# Servosolenoidvalve_of_Tatebayashi.net
KiCad netlist of a schematic drawn in EAGLE
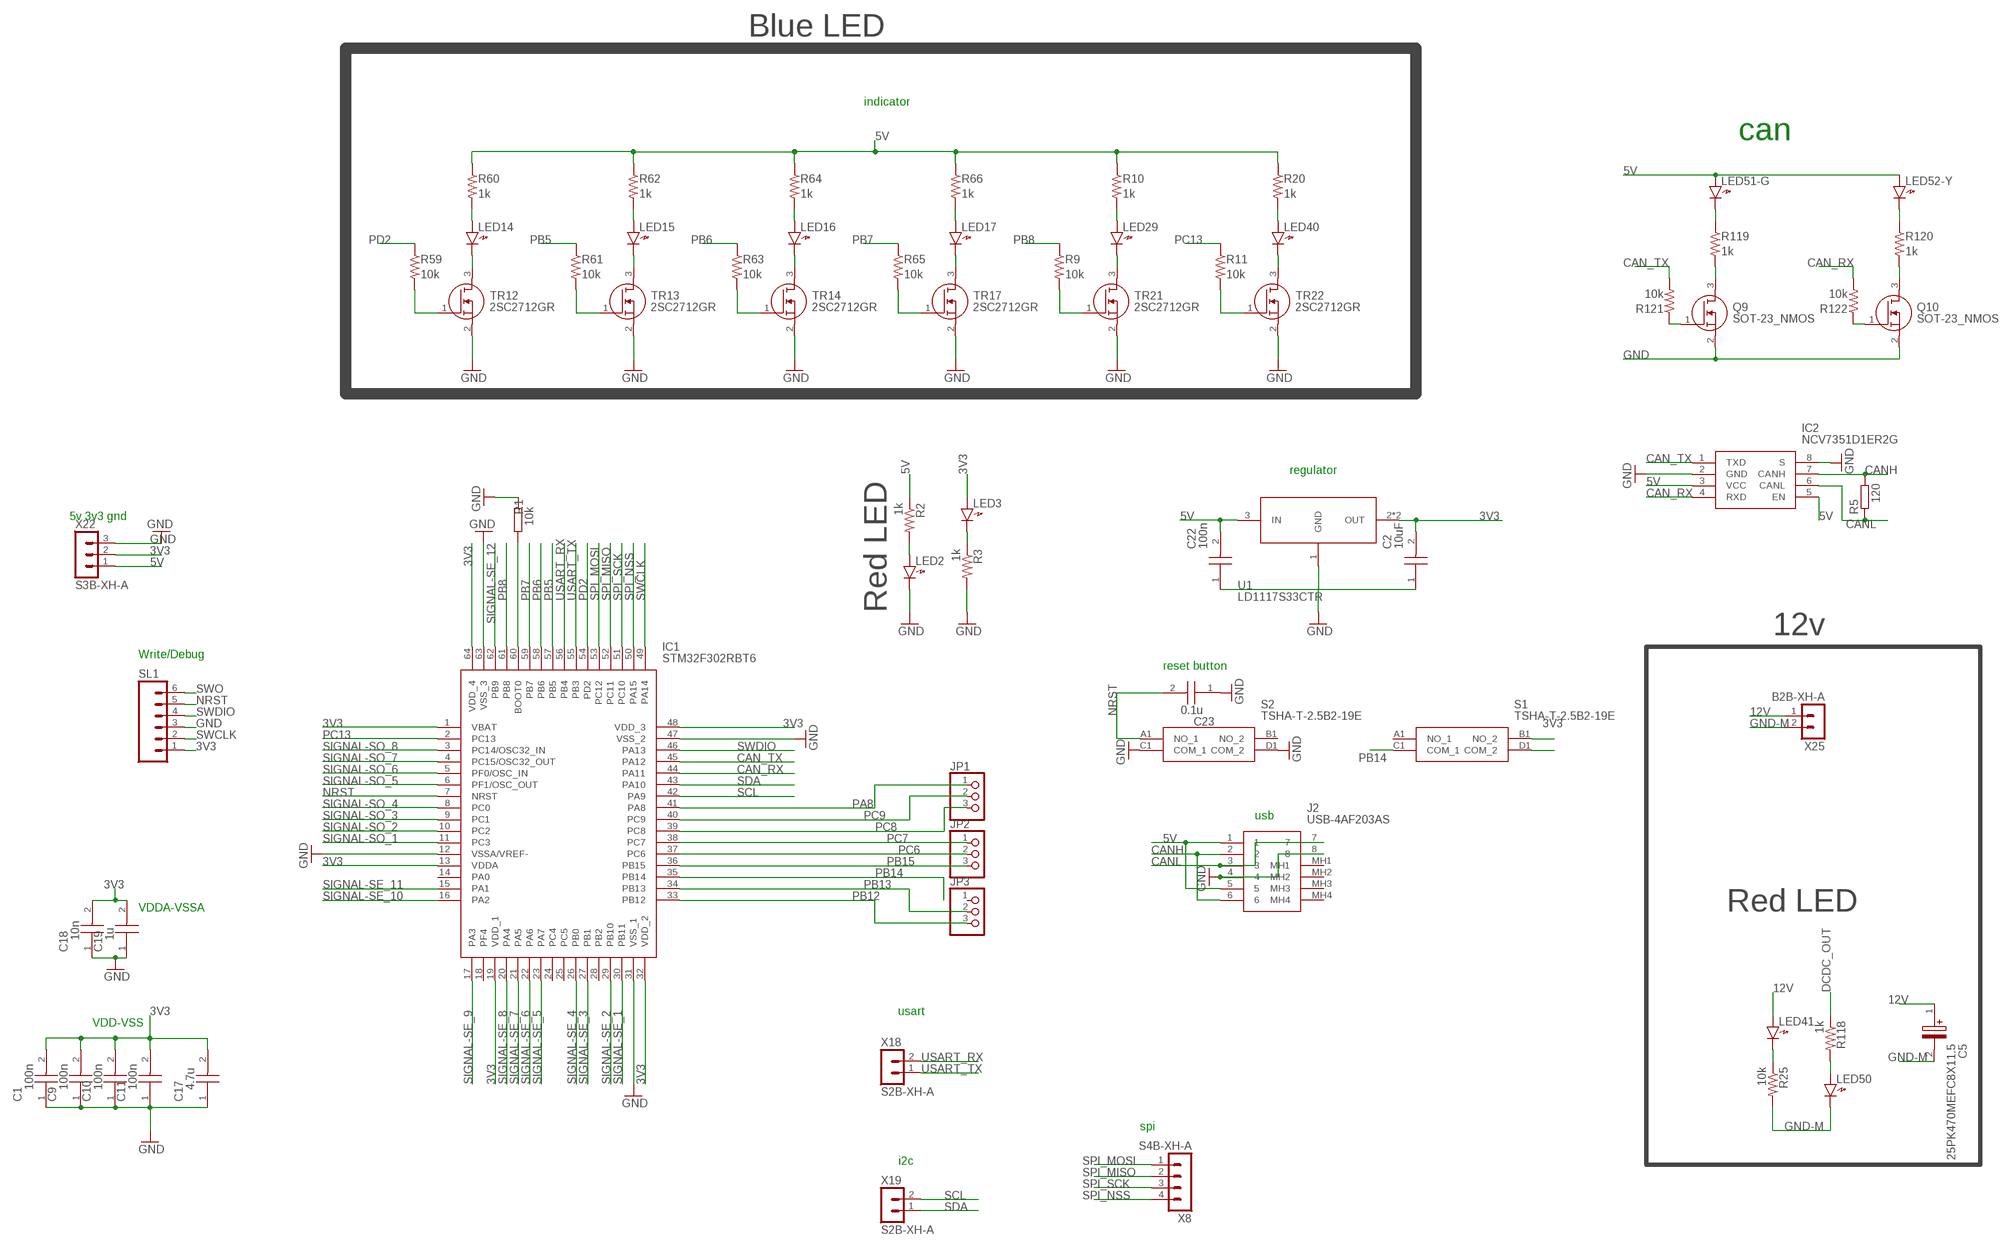
[diagram p0: schematic, sheet 1]
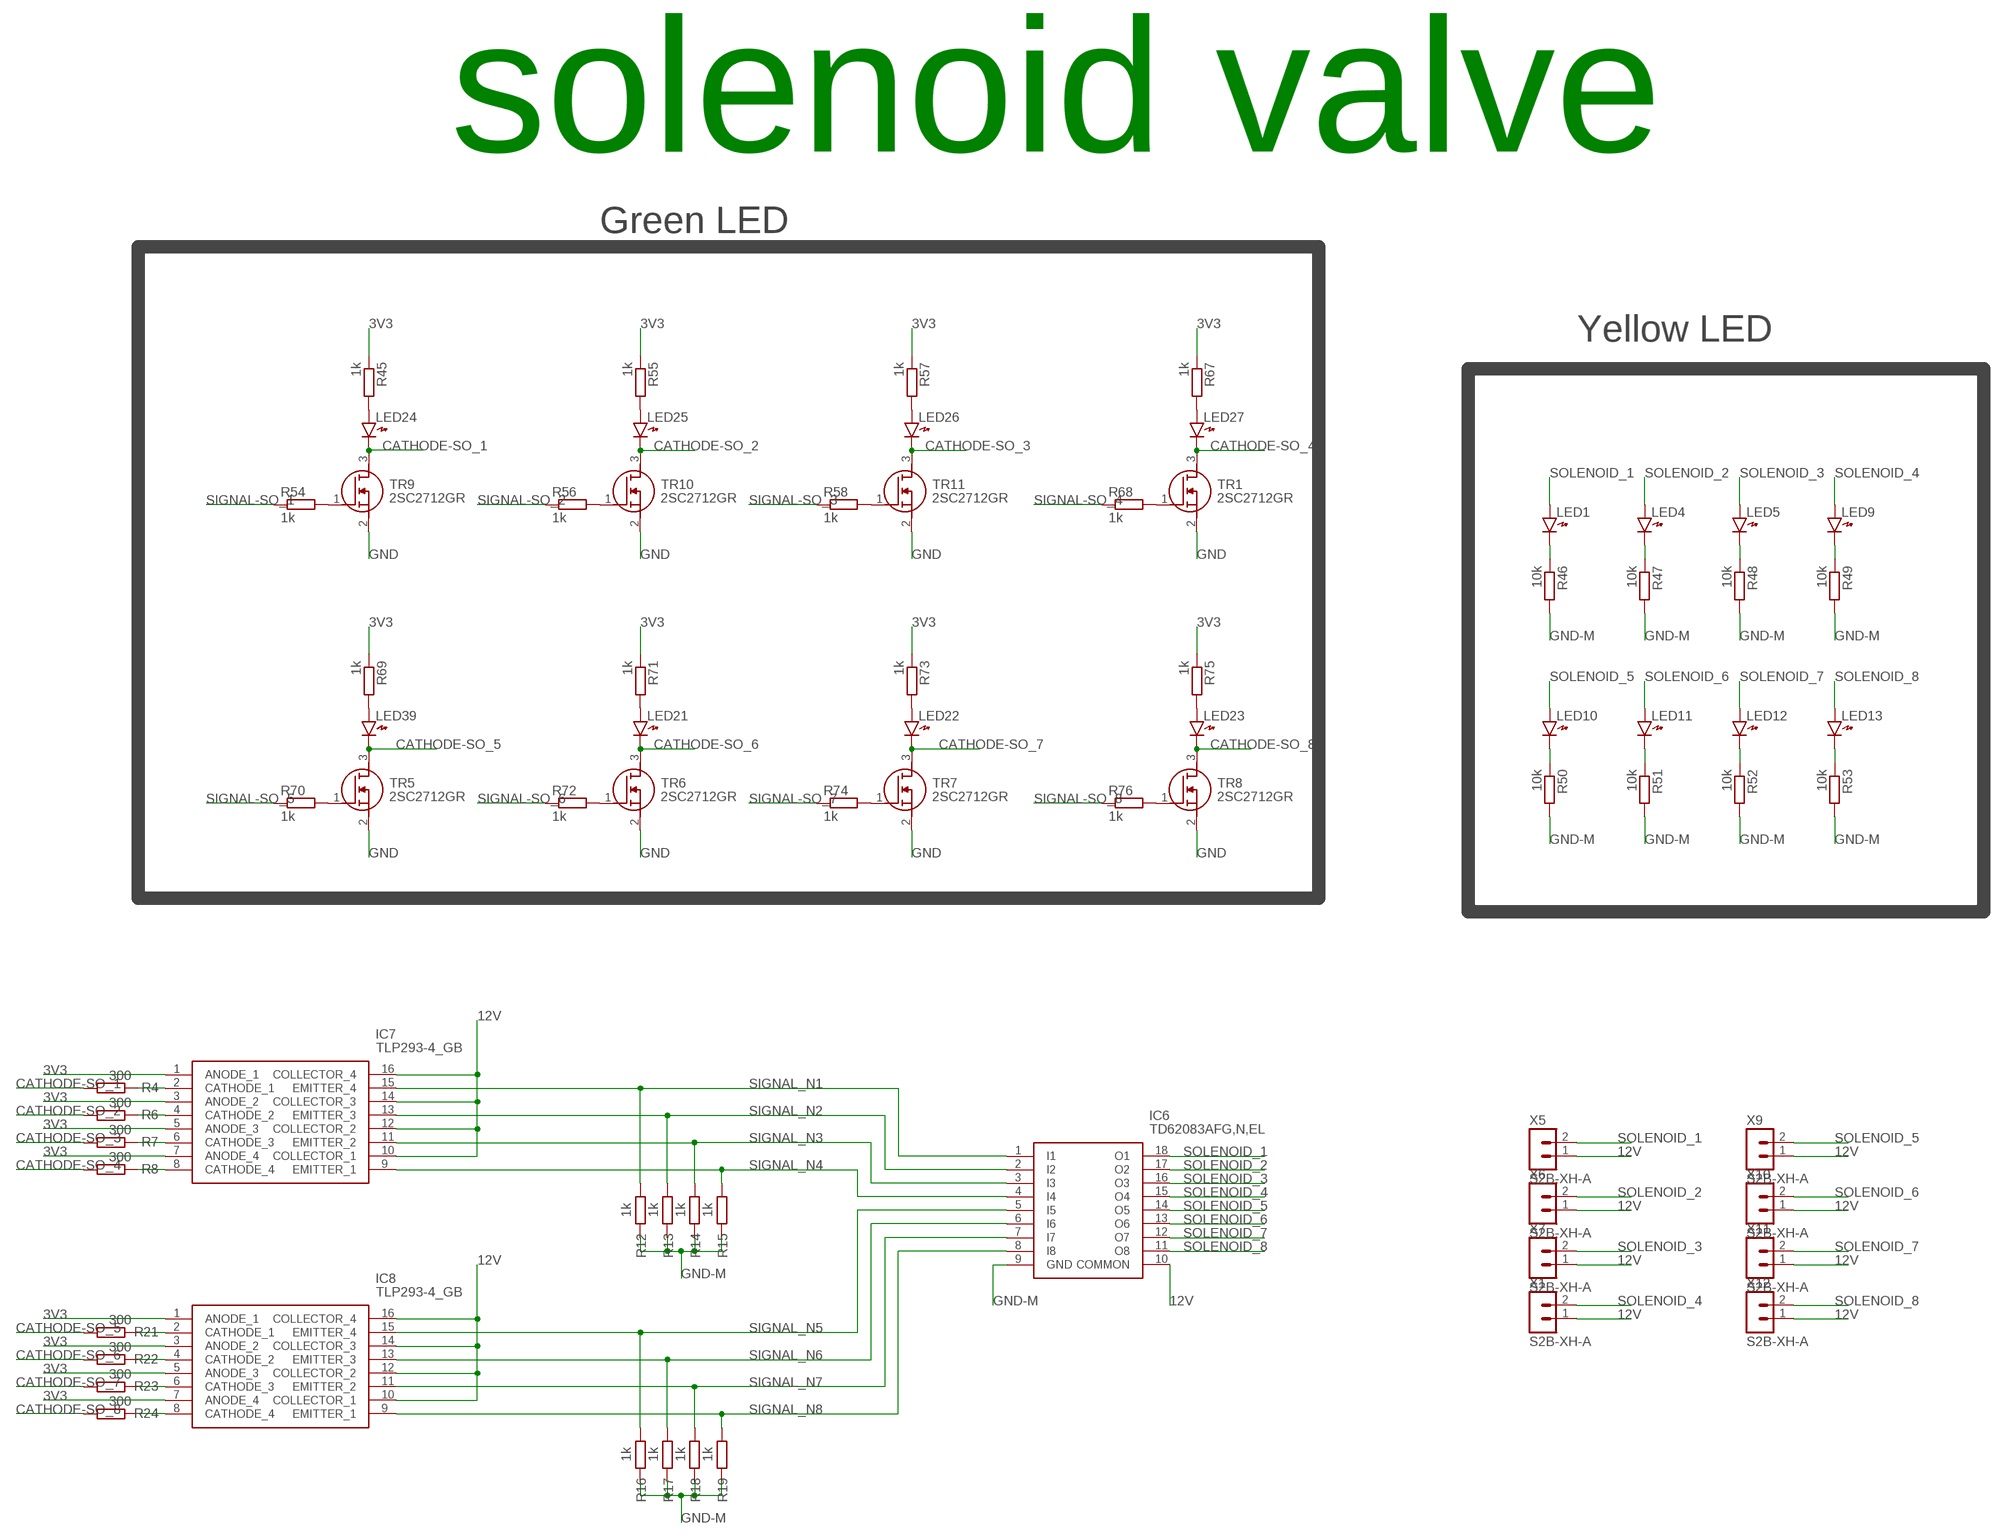
[diagram p1: schematic, sheet 2]
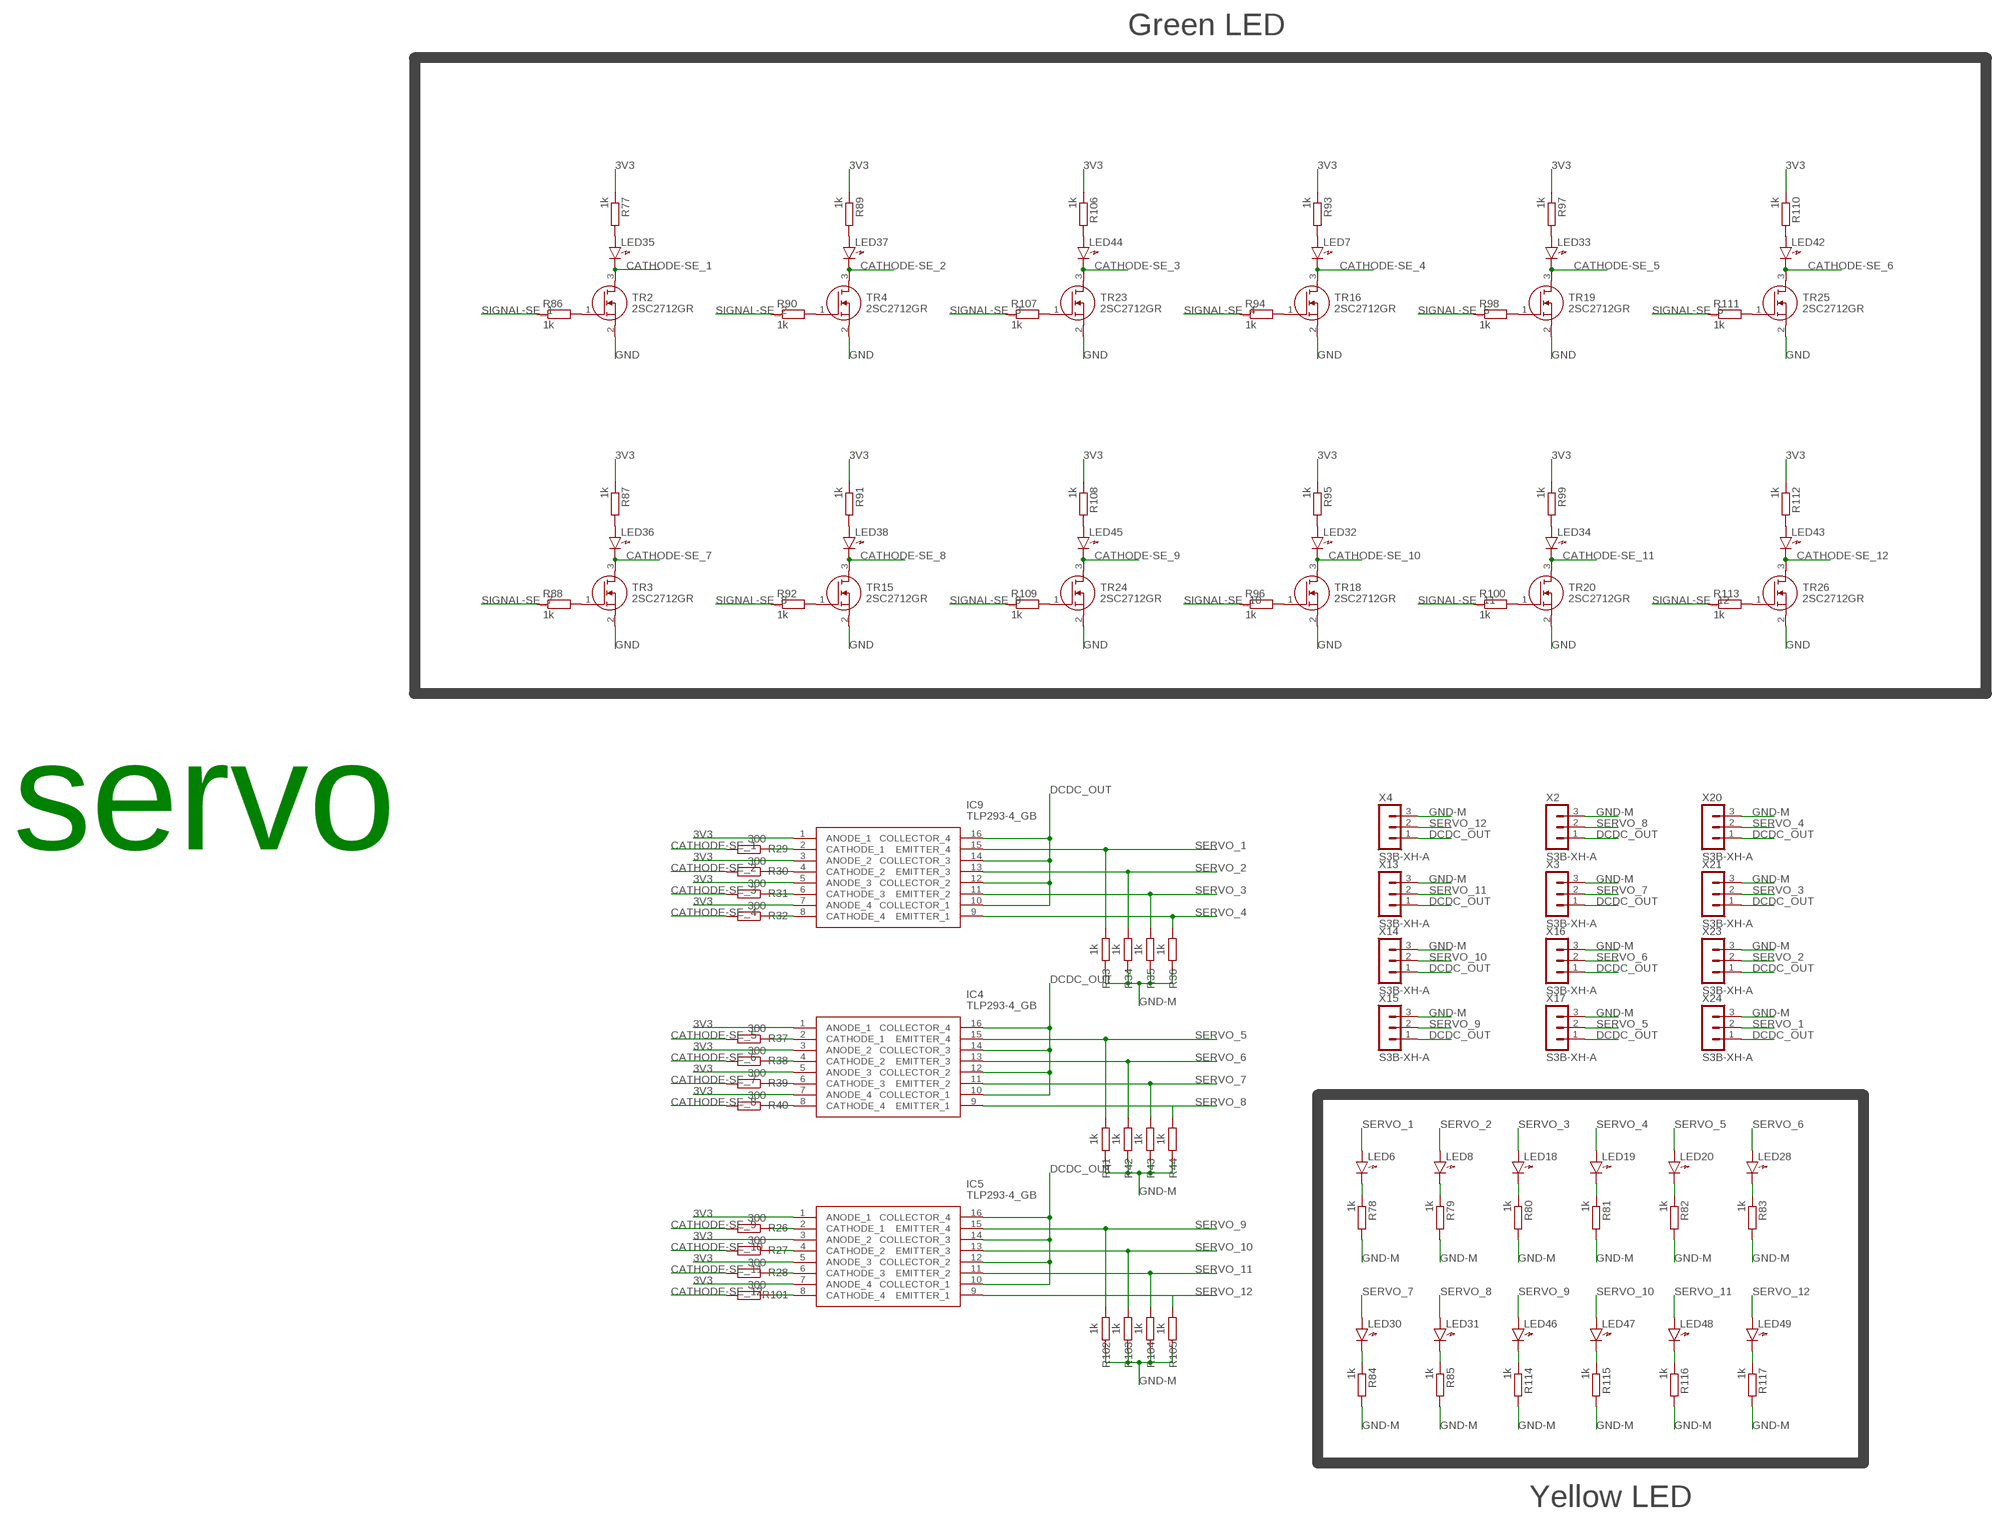
[diagram p2: schematic, sheet 3]

(export (version "E")
  (design (tool "Eeschema 10.0.6"))
  (components
    (comp (ref "IC6")
      (value "TD62083AFG,N,EL")
      (footprint "eagle-import:SOIC127P1030X245-18N")
      (libsource (lib "eagle-import") (part "TD62083AFG,N,EL"))
    )
    (comp (ref "IC7")
      (value "TLP293-4_GB")
      (footprint "eagle-import:SOP128P700X220-16N")
      (fields (field (name "MANUFACTURER_PART_NUMBER") "TLP293-4(GB"))
      (libsource (lib "eagle-import") (part "TLP293-4_GB"))
    )
    (comp (ref "IC8")
      (value "TLP293-4_GB")
      (footprint "eagle-import:SOP128P700X220-16N")
      (fields (field (name "MANUFACTURER_PART_NUMBER") "TLP293-4(GB"))
      (libsource (lib "eagle-import") (part "TLP293-4_GB"))
    )
    (comp (ref "LED1")
      (value "LED1608")
      (footprint "eagle-import:LED1608")
      (libsource (lib "eagle-import") (part "LED1608"))
    )
    (comp (ref "LED4")
      (value "LED1608")
      (footprint "eagle-import:LED1608")
      (libsource (lib "eagle-import") (part "LED1608"))
    )
    (comp (ref "LED5")
      (value "LED1608")
      (footprint "eagle-import:LED1608")
      (libsource (lib "eagle-import") (part "LED1608"))
    )
    (comp (ref "LED9")
      (value "LED1608")
      (footprint "eagle-import:LED1608")
      (libsource (lib "eagle-import") (part "LED1608"))
    )
    (comp (ref "LED10")
      (value "LED1608")
      (footprint "eagle-import:LED1608")
      (libsource (lib "eagle-import") (part "LED1608"))
    )
    (comp (ref "LED11")
      (value "LED1608")
      (footprint "eagle-import:LED1608")
      (libsource (lib "eagle-import") (part "LED1608"))
    )
    (comp (ref "LED12")
      (value "LED1608")
      (footprint "eagle-import:LED1608")
      (libsource (lib "eagle-import") (part "LED1608"))
    )
    (comp (ref "LED13")
      (value "LED1608")
      (footprint "eagle-import:LED1608")
      (libsource (lib "eagle-import") (part "LED1608"))
    )
    (comp (ref "LED21")
      (value "LED1608")
      (footprint "eagle-import:LED1608")
      (libsource (lib "eagle-import") (part "LED1608"))
    )
    (comp (ref "LED22")
      (value "LED1608")
      (footprint "eagle-import:LED1608")
      (libsource (lib "eagle-import") (part "LED1608"))
    )
    (comp (ref "LED23")
      (value "LED1608")
      (footprint "eagle-import:LED1608")
      (libsource (lib "eagle-import") (part "LED1608"))
    )
    (comp (ref "LED24")
      (value "LED1608")
      (footprint "eagle-import:LED1608")
      (libsource (lib "eagle-import") (part "LED1608"))
    )
    (comp (ref "LED25")
      (value "LED1608")
      (footprint "eagle-import:LED1608")
      (libsource (lib "eagle-import") (part "LED1608"))
    )
    (comp (ref "LED26")
      (value "LED1608")
      (footprint "eagle-import:LED1608")
      (libsource (lib "eagle-import") (part "LED1608"))
    )
    (comp (ref "LED27")
      (value "LED1608")
      (footprint "eagle-import:LED1608")
      (libsource (lib "eagle-import") (part "LED1608"))
    )
    (comp (ref "LED39")
      (value "LED1608")
      (footprint "eagle-import:LED1608")
      (libsource (lib "eagle-import") (part "LED1608"))
    )
    (comp (ref "R4")
      (value "300")
      (footprint "eagle-import:R0603")
      (libsource (lib "eagle-import") (part "R-EU_R0603"))
    )
    (comp (ref "R6")
      (value "300")
      (footprint "eagle-import:R0603")
      (libsource (lib "eagle-import") (part "R-EU_R0603"))
    )
    (comp (ref "R7")
      (value "300")
      (footprint "eagle-import:R0603")
      (libsource (lib "eagle-import") (part "R-EU_R0603"))
    )
    (comp (ref "R8")
      (value "300")
      (footprint "eagle-import:R0603")
      (libsource (lib "eagle-import") (part "R-EU_R0603"))
    )
    (comp (ref "R12")
      (value "1k")
      (footprint "eagle-import:R0603")
      (libsource (lib "eagle-import") (part "R-EU_R0603"))
    )
    (comp (ref "R13")
      (value "1k")
      (footprint "eagle-import:R0603")
      (libsource (lib "eagle-import") (part "R-EU_R0603"))
    )
    (comp (ref "R14")
      (value "1k")
      (footprint "eagle-import:R0603")
      (libsource (lib "eagle-import") (part "R-EU_R0603"))
    )
    (comp (ref "R15")
      (value "1k")
      (footprint "eagle-import:R0603")
      (libsource (lib "eagle-import") (part "R-EU_R0603"))
    )
    (comp (ref "R16")
      (value "1k")
      (footprint "eagle-import:R0603")
      (libsource (lib "eagle-import") (part "R-EU_R0603"))
    )
    (comp (ref "R17")
      (value "1k")
      (footprint "eagle-import:R0603")
      (libsource (lib "eagle-import") (part "R-EU_R0603"))
    )
    (comp (ref "R18")
      (value "1k")
      (footprint "eagle-import:R0603")
      (libsource (lib "eagle-import") (part "R-EU_R0603"))
    )
    (comp (ref "R19")
      (value "1k")
      (footprint "eagle-import:R0603")
      (libsource (lib "eagle-import") (part "R-EU_R0603"))
    )
    (comp (ref "R21")
      (value "300")
      (footprint "eagle-import:R0603")
      (libsource (lib "eagle-import") (part "R-EU_R0603"))
    )
    (comp (ref "R22")
      (value "300")
      (footprint "eagle-import:R0603")
      (libsource (lib "eagle-import") (part "R-EU_R0603"))
    )
    (comp (ref "R23")
      (value "300")
      (footprint "eagle-import:R0603")
      (libsource (lib "eagle-import") (part "R-EU_R0603"))
    )
    (comp (ref "R24")
      (value "300")
      (footprint "eagle-import:R0603")
      (libsource (lib "eagle-import") (part "R-EU_R0603"))
    )
    (comp (ref "R45")
      (value "1k")
      (footprint "eagle-import:R0603")
      (libsource (lib "eagle-import") (part "R-EU_R0603"))
    )
    (comp (ref "R46")
      (value "10k")
      (footprint "eagle-import:R0603")
      (libsource (lib "eagle-import") (part "R-EU_R0603"))
    )
    (comp (ref "R47")
      (value "10k")
      (footprint "eagle-import:R0603")
      (libsource (lib "eagle-import") (part "R-EU_R0603"))
    )
    (comp (ref "R48")
      (value "10k")
      (footprint "eagle-import:R0603")
      (libsource (lib "eagle-import") (part "R-EU_R0603"))
    )
    (comp (ref "R49")
      (value "10k")
      (footprint "eagle-import:R0603")
      (libsource (lib "eagle-import") (part "R-EU_R0603"))
    )
    (comp (ref "R50")
      (value "10k")
      (footprint "eagle-import:R0603")
      (libsource (lib "eagle-import") (part "R-EU_R0603"))
    )
    (comp (ref "R51")
      (value "10k")
      (footprint "eagle-import:R0603")
      (libsource (lib "eagle-import") (part "R-EU_R0603"))
    )
    (comp (ref "R52")
      (value "10k")
      (footprint "eagle-import:R0603")
      (libsource (lib "eagle-import") (part "R-EU_R0603"))
    )
    (comp (ref "R53")
      (value "10k")
      (footprint "eagle-import:R0603")
      (libsource (lib "eagle-import") (part "R-EU_R0603"))
    )
    (comp (ref "R54")
      (value "1k")
      (footprint "eagle-import:R0603")
      (libsource (lib "eagle-import") (part "R-EU_R0603"))
    )
    (comp (ref "R55")
      (value "1k")
      (footprint "eagle-import:R0603")
      (libsource (lib "eagle-import") (part "R-EU_R0603"))
    )
    (comp (ref "R56")
      (value "1k")
      (footprint "eagle-import:R0603")
      (libsource (lib "eagle-import") (part "R-EU_R0603"))
    )
    (comp (ref "R57")
      (value "1k")
      (footprint "eagle-import:R0603")
      (libsource (lib "eagle-import") (part "R-EU_R0603"))
    )
    (comp (ref "R58")
      (value "1k")
      (footprint "eagle-import:R0603")
      (libsource (lib "eagle-import") (part "R-EU_R0603"))
    )
    (comp (ref "R67")
      (value "1k")
      (footprint "eagle-import:R0603")
      (libsource (lib "eagle-import") (part "R-EU_R0603"))
    )
    (comp (ref "R68")
      (value "1k")
      (footprint "eagle-import:R0603")
      (libsource (lib "eagle-import") (part "R-EU_R0603"))
    )
    (comp (ref "R69")
      (value "1k")
      (footprint "eagle-import:R0603")
      (libsource (lib "eagle-import") (part "R-EU_R0603"))
    )
    (comp (ref "R70")
      (value "1k")
      (footprint "eagle-import:R0603")
      (libsource (lib "eagle-import") (part "R-EU_R0603"))
    )
    (comp (ref "R71")
      (value "1k")
      (footprint "eagle-import:R0603")
      (libsource (lib "eagle-import") (part "R-EU_R0603"))
    )
    (comp (ref "R72")
      (value "1k")
      (footprint "eagle-import:R0603")
      (libsource (lib "eagle-import") (part "R-EU_R0603"))
    )
    (comp (ref "R73")
      (value "1k")
      (footprint "eagle-import:R0603")
      (libsource (lib "eagle-import") (part "R-EU_R0603"))
    )
    (comp (ref "R74")
      (value "1k")
      (footprint "eagle-import:R0603")
      (libsource (lib "eagle-import") (part "R-EU_R0603"))
    )
    (comp (ref "R75")
      (value "1k")
      (footprint "eagle-import:R0603")
      (libsource (lib "eagle-import") (part "R-EU_R0603"))
    )
    (comp (ref "R76")
      (value "1k")
      (footprint "eagle-import:R0603")
      (libsource (lib "eagle-import") (part "R-EU_R0603"))
    )
    (comp (ref "TR1")
      (value "2SC2712GR")
      (footprint "eagle-import:SOT-23")
      (libsource (lib "eagle-import") (part "SOT-23_NMOS"))
    )
    (comp (ref "TR5")
      (value "2SC2712GR")
      (footprint "eagle-import:SOT-23")
      (libsource (lib "eagle-import") (part "SOT-23_NMOS"))
    )
    (comp (ref "TR6")
      (value "2SC2712GR")
      (footprint "eagle-import:SOT-23")
      (libsource (lib "eagle-import") (part "SOT-23_NMOS"))
    )
    (comp (ref "TR7")
      (value "2SC2712GR")
      (footprint "eagle-import:SOT-23")
      (libsource (lib "eagle-import") (part "SOT-23_NMOS"))
    )
    (comp (ref "TR8")
      (value "2SC2712GR")
      (footprint "eagle-import:SOT-23")
      (libsource (lib "eagle-import") (part "SOT-23_NMOS"))
    )
    (comp (ref "TR9")
      (value "2SC2712GR")
      (footprint "eagle-import:SOT-23")
      (libsource (lib "eagle-import") (part "SOT-23_NMOS"))
    )
    (comp (ref "TR10")
      (value "2SC2712GR")
      (footprint "eagle-import:SOT-23")
      (libsource (lib "eagle-import") (part "SOT-23_NMOS"))
    )
    (comp (ref "TR11")
      (value "2SC2712GR")
      (footprint "eagle-import:SOT-23")
      (libsource (lib "eagle-import") (part "SOT-23_NMOS"))
    )
    (comp (ref "X1")
      (value "S2B-XH-A")
      (footprint "eagle-import:S2B-XH-A")
      (libsource (lib "eagle-import") (part "S2B-XH-A"))
    )
    (comp (ref "X5")
      (value "S2B-XH-A")
      (footprint "eagle-import:S2B-XH-A")
      (libsource (lib "eagle-import") (part "S2B-XH-A"))
    )
    (comp (ref "X6")
      (value "S2B-XH-A")
      (footprint "eagle-import:S2B-XH-A")
      (libsource (lib "eagle-import") (part "S2B-XH-A"))
    )
    (comp (ref "X7")
      (value "S2B-XH-A")
      (footprint "eagle-import:S2B-XH-A")
      (libsource (lib "eagle-import") (part "S2B-XH-A"))
    )
    (comp (ref "X9")
      (value "S2B-XH-A")
      (footprint "eagle-import:S2B-XH-A")
      (libsource (lib "eagle-import") (part "S2B-XH-A"))
    )
    (comp (ref "X10")
      (value "S2B-XH-A")
      (footprint "eagle-import:S2B-XH-A")
      (libsource (lib "eagle-import") (part "S2B-XH-A"))
    )
    (comp (ref "X11")
      (value "S2B-XH-A")
      (footprint "eagle-import:S2B-XH-A")
      (libsource (lib "eagle-import") (part "S2B-XH-A"))
    )
    (comp (ref "X12")
      (value "S2B-XH-A")
      (footprint "eagle-import:S2B-XH-A")
      (libsource (lib "eagle-import") (part "S2B-XH-A"))
    )
    (comp (ref "C1")
      (value "100n")
      (footprint "eagle-import:CAPC1709X100N")
      (fields
        (field (name "MANUFACTURER_PART_NUMBER") "AMK107BBJ476MA-RE")
        (field (name "MOUSER_PART_NUMBER") "963-AMK107BBJ476MARE")
        (field (name "RS_PART_NUMBER") "1843762P")
      )
      (libsource (lib "eagle-import") (part "AMK107BBJ476MA-RE"))
    )
    (comp (ref "C2")
      (value "10uF")
      (footprint "eagle-import:CAPC1608X90N")
      (fields
        (field (name "MANUFACTURER_PART_NUMBER") "GRM188B31A106KE69D")
        (field (name "RS_PART_NUMBER") "8847157P")
      )
      (libsource (lib "eagle-import") (part "GRM188B31A106KE69D"))
    )
    (comp (ref "C5")
      (value "25PK470MEFC8X11.5")
      (footprint "eagle-import:CAPPRD350W60D825H1150")
      (fields (field (name "MOUSER_PART_NUMBER") "232-25PK470MEFC8X115"))
      (libsource (lib "eagle-import") (part "25PK470MEFC8X11.5"))
    )
    (comp (ref "C9")
      (value "100n")
      (footprint "eagle-import:CAPC1709X100N")
      (fields
        (field (name "MANUFACTURER_PART_NUMBER") "AMK107BBJ476MA-RE")
        (field (name "MOUSER_PART_NUMBER") "963-AMK107BBJ476MARE")
        (field (name "RS_PART_NUMBER") "1843762P")
      )
      (libsource (lib "eagle-import") (part "AMK107BBJ476MA-RE"))
    )
    (comp (ref "C10")
      (value "100n")
      (footprint "eagle-import:CAPC1709X100N")
      (fields
        (field (name "MANUFACTURER_PART_NUMBER") "AMK107BBJ476MA-RE")
        (field (name "MOUSER_PART_NUMBER") "963-AMK107BBJ476MARE")
        (field (name "RS_PART_NUMBER") "1843762P")
      )
      (libsource (lib "eagle-import") (part "AMK107BBJ476MA-RE"))
    )
    (comp (ref "C11")
      (value "100n")
      (footprint "eagle-import:CAPC1709X100N")
      (fields
        (field (name "MANUFACTURER_PART_NUMBER") "AMK107BBJ476MA-RE")
        (field (name "MOUSER_PART_NUMBER") "963-AMK107BBJ476MARE")
        (field (name "RS_PART_NUMBER") "1843762P")
      )
      (libsource (lib "eagle-import") (part "AMK107BBJ476MA-RE"))
    )
    (comp (ref "C17")
      (value "4.7u")
      (footprint "eagle-import:CAPC1709X100N")
      (fields
        (field (name "MANUFACTURER_PART_NUMBER") "AMK107BBJ476MA-RE")
        (field (name "MOUSER_PART_NUMBER") "963-AMK107BBJ476MARE")
        (field (name "RS_PART_NUMBER") "1843762P")
      )
      (libsource (lib "eagle-import") (part "AMK107BBJ476MA-RE"))
    )
    (comp (ref "C18")
      (value "10n")
      (footprint "eagle-import:CAPC1709X100N")
      (fields
        (field (name "MANUFACTURER_PART_NUMBER") "AMK107BBJ476MA-RE")
        (field (name "MOUSER_PART_NUMBER") "963-AMK107BBJ476MARE")
        (field (name "RS_PART_NUMBER") "1843762P")
      )
      (libsource (lib "eagle-import") (part "AMK107BBJ476MA-RE"))
    )
    (comp (ref "C19")
      (value "1u")
      (footprint "eagle-import:CAPC1709X100N")
      (fields
        (field (name "MANUFACTURER_PART_NUMBER") "AMK107BBJ476MA-RE")
        (field (name "MOUSER_PART_NUMBER") "963-AMK107BBJ476MARE")
        (field (name "RS_PART_NUMBER") "1843762P")
      )
      (libsource (lib "eagle-import") (part "AMK107BBJ476MA-RE"))
    )
    (comp (ref "C22")
      (value "100n")
      (footprint "eagle-import:CAPC1608X90N")
      (fields
        (field (name "MANUFACTURER_PART_NUMBER") "GRM188B31A106KE69D")
        (field (name "RS_PART_NUMBER") "8847157P")
      )
      (libsource (lib "eagle-import") (part "GRM188B31A106KE69D"))
    )
    (comp (ref "C23")
      (value "0.1u")
      (footprint "eagle-import:CAPC1709X100N")
      (fields
        (field (name "MANUFACTURER_PART_NUMBER") "AMK107BBJ476MA-RE")
        (field (name "MOUSER_PART_NUMBER") "963-AMK107BBJ476MARE")
        (field (name "RS_PART_NUMBER") "1843762P")
      )
      (libsource (lib "eagle-import") (part "AMK107BBJ476MA-RE"))
    )
    (comp (ref "IC1")
      (value "STM32F302RBT6")
      (footprint "eagle-import:QFP50P1200X1200X160-64N")
      (fields (field (name "MOUSER_PART_NUMBER") "511-STM32F302RBT6"))
      (libsource (lib "eagle-import") (part "STM32F302RBT6"))
    )
    (comp (ref "IC2")
      (value "NCV7351D1ER2G")
      (footprint "eagle-import:SOIC127P600X175-8N")
      (fields (field (name "MOUSER_PART_NUMBER") "863-NCV7351D1ER2G"))
      (libsource (lib "eagle-import") (part "NCV7351D1ER2G"))
    )
    (comp (ref "J2")
      (value "USB-4AF203AS")
      (footprint "eagle-import:USB4AF203AS")
      (libsource (lib "eagle-import") (part "USB-4AF203AS"))
    )
    (comp (ref "JP1")
      (value "PINHD-1X3")
      (footprint "eagle-import:1X03")
      (libsource (lib "eagle-import") (part "PINHD-1X3"))
    )
    (comp (ref "JP2")
      (value "PINHD-1X3")
      (footprint "eagle-import:1X03")
      (libsource (lib "eagle-import") (part "PINHD-1X3"))
    )
    (comp (ref "JP3")
      (value "PINHD-1X3")
      (footprint "eagle-import:1X03")
      (libsource (lib "eagle-import") (part "PINHD-1X3"))
    )
    (comp (ref "LED2")
      (value "LED1608")
      (footprint "eagle-import:LED1608")
      (libsource (lib "eagle-import") (part "LED1608"))
    )
    (comp (ref "LED3")
      (value "LED1608")
      (footprint "eagle-import:LED1608")
      (libsource (lib "eagle-import") (part "LED1608"))
    )
    (comp (ref "LED14")
      (value "LED1608")
      (footprint "eagle-import:LED1608")
      (libsource (lib "eagle-import") (part "LED1608"))
    )
    (comp (ref "LED15")
      (value "LED1608")
      (footprint "eagle-import:LED1608")
      (libsource (lib "eagle-import") (part "LED1608"))
    )
    (comp (ref "LED16")
      (value "LED1608")
      (footprint "eagle-import:LED1608")
      (libsource (lib "eagle-import") (part "LED1608"))
    )
    (comp (ref "LED17")
      (value "LED1608")
      (footprint "eagle-import:LED1608")
      (libsource (lib "eagle-import") (part "LED1608"))
    )
    (comp (ref "LED29")
      (value "LED1608")
      (footprint "eagle-import:LED1608")
      (libsource (lib "eagle-import") (part "LED1608"))
    )
    (comp (ref "LED40")
      (value "LED1608")
      (footprint "eagle-import:LED1608")
      (libsource (lib "eagle-import") (part "LED1608"))
    )
    (comp (ref "LED41")
      (value "LED1608")
      (footprint "eagle-import:LED1608")
      (libsource (lib "eagle-import") (part "LED1608"))
    )
    (comp (ref "LED50")
      (value "LED1608")
      (footprint "eagle-import:LED1608")
      (libsource (lib "eagle-import") (part "LED1608"))
    )
    (comp (ref "LED51-G")
      (value "LED1608")
      (footprint "eagle-import:LED1608")
      (libsource (lib "eagle-import") (part "LED1608"))
    )
    (comp (ref "LED52-Y")
      (value "LED1608")
      (footprint "eagle-import:LED1608")
      (libsource (lib "eagle-import") (part "LED1608"))
    )
    (comp (ref "Q9")
      (value "SOT-23_NMOS")
      (footprint "eagle-import:SOT-23")
      (libsource (lib "eagle-import") (part "SOT-23_NMOS"))
    )
    (comp (ref "Q10")
      (value "SOT-23_NMOS")
      (footprint "eagle-import:SOT-23")
      (libsource (lib "eagle-import") (part "SOT-23_NMOS"))
    )
    (comp (ref "R1")
      (value "10k")
      (footprint "eagle-import:1608")
      (libsource (lib "eagle-import") (part "R1608"))
    )
    (comp (ref "R2")
      (value "1k")
      (footprint "eagle-import:R0603")
      (libsource (lib "eagle-import") (part "R-US_R0603"))
    )
    (comp (ref "R3")
      (value "1k")
      (footprint "eagle-import:R0603")
      (libsource (lib "eagle-import") (part "R-US_R0603"))
    )
    (comp (ref "R5")
      (value "120")
      (footprint "eagle-import:R0805")
      (libsource (lib "eagle-import") (part "R-EU_R0805"))
    )
    (comp (ref "R9")
      (value "10k")
      (footprint "eagle-import:SMD1608")
      (libsource (lib "eagle-import") (part "RESISTOR-US1608"))
    )
    (comp (ref "R10")
      (value "1k")
      (footprint "eagle-import:SMD1608")
      (libsource (lib "eagle-import") (part "RESISTOR-US1608"))
    )
    (comp (ref "R11")
      (value "10k")
      (footprint "eagle-import:SMD1608")
      (libsource (lib "eagle-import") (part "RESISTOR-US1608"))
    )
    (comp (ref "R20")
      (value "1k")
      (footprint "eagle-import:SMD1608")
      (libsource (lib "eagle-import") (part "RESISTOR-US1608"))
    )
    (comp (ref "R25")
      (value "10k")
      (footprint "eagle-import:R0603")
      (libsource (lib "eagle-import") (part "R-US_R0603"))
    )
    (comp (ref "R59")
      (value "10k")
      (footprint "eagle-import:SMD1608")
      (libsource (lib "eagle-import") (part "RESISTOR-US1608"))
    )
    (comp (ref "R60")
      (value "1k")
      (footprint "eagle-import:SMD1608")
      (libsource (lib "eagle-import") (part "RESISTOR-US1608"))
    )
    (comp (ref "R61")
      (value "10k")
      (footprint "eagle-import:SMD1608")
      (libsource (lib "eagle-import") (part "RESISTOR-US1608"))
    )
    (comp (ref "R62")
      (value "1k")
      (footprint "eagle-import:SMD1608")
      (libsource (lib "eagle-import") (part "RESISTOR-US1608"))
    )
    (comp (ref "R63")
      (value "10k")
      (footprint "eagle-import:SMD1608")
      (libsource (lib "eagle-import") (part "RESISTOR-US1608"))
    )
    (comp (ref "R64")
      (value "1k")
      (footprint "eagle-import:SMD1608")
      (libsource (lib "eagle-import") (part "RESISTOR-US1608"))
    )
    (comp (ref "R65")
      (value "10k")
      (footprint "eagle-import:SMD1608")
      (libsource (lib "eagle-import") (part "RESISTOR-US1608"))
    )
    (comp (ref "R66")
      (value "1k")
      (footprint "eagle-import:SMD1608")
      (libsource (lib "eagle-import") (part "RESISTOR-US1608"))
    )
    (comp (ref "R118")
      (value "1k")
      (footprint "eagle-import:R0603")
      (libsource (lib "eagle-import") (part "R-US_R0603"))
    )
    (comp (ref "R119")
      (value "1k")
      (footprint "eagle-import:SMD1608")
      (libsource (lib "eagle-import") (part "RESISTOR-US1608"))
    )
    (comp (ref "R120")
      (value "1k")
      (footprint "eagle-import:SMD1608")
      (libsource (lib "eagle-import") (part "RESISTOR-US1608"))
    )
    (comp (ref "R121")
      (value "10k")
      (footprint "eagle-import:SMD1608")
      (libsource (lib "eagle-import") (part "RESISTOR-US1608"))
    )
    (comp (ref "R122")
      (value "10k")
      (footprint "eagle-import:SMD1608")
      (libsource (lib "eagle-import") (part "RESISTOR-US1608"))
    )
    (comp (ref "S1")
      (value "TSHA-T-2.5B2-19E")
      (footprint "eagle-import:TSHAT25B219E")
      (libsource (lib "eagle-import") (part "TSHA-T-2.5B2-19E"))
    )
    (comp (ref "S2")
      (value "TSHA-T-2.5B2-19E")
      (footprint "eagle-import:TSHAT25B219E")
      (libsource (lib "eagle-import") (part "TSHA-T-2.5B2-19E"))
    )
    (comp (ref "SL1")
      (value "MA06")
      (footprint "eagle-import:06PA")
      (libsource (lib "eagle-import") (part "MA06"))
    )
    (comp (ref "TR12")
      (value "2SC2712GR")
      (footprint "eagle-import:SOT-23")
      (libsource (lib "eagle-import") (part "SOT-23_NMOS"))
    )
    (comp (ref "TR13")
      (value "2SC2712GR")
      (footprint "eagle-import:SOT-23")
      (libsource (lib "eagle-import") (part "SOT-23_NMOS"))
    )
    (comp (ref "TR14")
      (value "2SC2712GR")
      (footprint "eagle-import:SOT-23")
      (libsource (lib "eagle-import") (part "SOT-23_NMOS"))
    )
    (comp (ref "TR17")
      (value "2SC2712GR")
      (footprint "eagle-import:SOT-23")
      (libsource (lib "eagle-import") (part "SOT-23_NMOS"))
    )
    (comp (ref "TR21")
      (value "2SC2712GR")
      (footprint "eagle-import:SOT-23")
      (libsource (lib "eagle-import") (part "SOT-23_NMOS"))
    )
    (comp (ref "TR22")
      (value "2SC2712GR")
      (footprint "eagle-import:SOT-23")
      (libsource (lib "eagle-import") (part "SOT-23_NMOS"))
    )
    (comp (ref "U1")
      (value "LD1117S33CTR")
      (footprint "eagle-import:SOT223")
      (fields (field (name "MF") "STMicroelectronics"))
      (libsource (lib "eagle-import") (part "LD1117S33CTR"))
    )
    (comp (ref "X8")
      (value "S4B-XH-A")
      (footprint "eagle-import:S4B-XH-A")
      (libsource (lib "eagle-import") (part "S4B-XH-A"))
    )
    (comp (ref "X18")
      (value "S2B-XH-A")
      (footprint "eagle-import:S2B-XH-A")
      (libsource (lib "eagle-import") (part "S2B-XH-A"))
    )
    (comp (ref "X19")
      (value "S2B-XH-A")
      (footprint "eagle-import:S2B-XH-A")
      (libsource (lib "eagle-import") (part "S2B-XH-A"))
    )
    (comp (ref "X22")
      (value "S3B-XH-A")
      (footprint "eagle-import:S3B-XH-A")
      (libsource (lib "eagle-import") (part "S3B-XH-A"))
    )
    (comp (ref "X25")
      (value "B2B-XH-A")
      (footprint "eagle-import:B2B-XH-A")
      (libsource (lib "eagle-import") (part "B2B-XH-A"))
    )
    (comp (ref "IC4")
      (value "TLP293-4_GB")
      (footprint "eagle-import:SOP128P700X220-16N")
      (fields (field (name "MANUFACTURER_PART_NUMBER") "TLP293-4(GB"))
      (libsource (lib "eagle-import") (part "TLP293-4_GB"))
    )
    (comp (ref "IC5")
      (value "TLP293-4_GB")
      (footprint "eagle-import:SOP128P700X220-16N")
      (fields (field (name "MANUFACTURER_PART_NUMBER") "TLP293-4(GB"))
      (libsource (lib "eagle-import") (part "TLP293-4_GB"))
    )
    (comp (ref "IC9")
      (value "TLP293-4_GB")
      (footprint "eagle-import:SOP128P700X220-16N")
      (fields (field (name "MANUFACTURER_PART_NUMBER") "TLP293-4(GB"))
      (libsource (lib "eagle-import") (part "TLP293-4_GB"))
    )
    (comp (ref "LED6")
      (value "LED1608")
      (footprint "eagle-import:LED1608")
      (libsource (lib "eagle-import") (part "LED1608"))
    )
    (comp (ref "LED7")
      (value "LED1608")
      (footprint "eagle-import:LED1608")
      (libsource (lib "eagle-import") (part "LED1608"))
    )
    (comp (ref "LED8")
      (value "LED1608")
      (footprint "eagle-import:LED1608")
      (libsource (lib "eagle-import") (part "LED1608"))
    )
    (comp (ref "LED18")
      (value "LED1608")
      (footprint "eagle-import:LED1608")
      (libsource (lib "eagle-import") (part "LED1608"))
    )
    (comp (ref "LED19")
      (value "LED1608")
      (footprint "eagle-import:LED1608")
      (libsource (lib "eagle-import") (part "LED1608"))
    )
    (comp (ref "LED20")
      (value "LED1608")
      (footprint "eagle-import:LED1608")
      (libsource (lib "eagle-import") (part "LED1608"))
    )
    (comp (ref "LED28")
      (value "LED1608")
      (footprint "eagle-import:LED1608")
      (libsource (lib "eagle-import") (part "LED1608"))
    )
    (comp (ref "LED30")
      (value "LED1608")
      (footprint "eagle-import:LED1608")
      (libsource (lib "eagle-import") (part "LED1608"))
    )
    (comp (ref "LED31")
      (value "LED1608")
      (footprint "eagle-import:LED1608")
      (libsource (lib "eagle-import") (part "LED1608"))
    )
    (comp (ref "LED32")
      (value "LED1608")
      (footprint "eagle-import:LED1608")
      (libsource (lib "eagle-import") (part "LED1608"))
    )
    (comp (ref "LED33")
      (value "LED1608")
      (footprint "eagle-import:LED1608")
      (libsource (lib "eagle-import") (part "LED1608"))
    )
    (comp (ref "LED34")
      (value "LED1608")
      (footprint "eagle-import:LED1608")
      (libsource (lib "eagle-import") (part "LED1608"))
    )
    (comp (ref "LED35")
      (value "LED1608")
      (footprint "eagle-import:LED1608")
      (libsource (lib "eagle-import") (part "LED1608"))
    )
    (comp (ref "LED36")
      (value "LED1608")
      (footprint "eagle-import:LED1608")
      (libsource (lib "eagle-import") (part "LED1608"))
    )
    (comp (ref "LED37")
      (value "LED1608")
      (footprint "eagle-import:LED1608")
      (libsource (lib "eagle-import") (part "LED1608"))
    )
    (comp (ref "LED38")
      (value "LED1608")
      (footprint "eagle-import:LED1608")
      (libsource (lib "eagle-import") (part "LED1608"))
    )
    (comp (ref "LED42")
      (value "LED1608")
      (footprint "eagle-import:LED1608")
      (libsource (lib "eagle-import") (part "LED1608"))
    )
    (comp (ref "LED43")
      (value "LED1608")
      (footprint "eagle-import:LED1608")
      (libsource (lib "eagle-import") (part "LED1608"))
    )
    (comp (ref "LED44")
      (value "LED1608")
      (footprint "eagle-import:LED1608")
      (libsource (lib "eagle-import") (part "LED1608"))
    )
    (comp (ref "LED45")
      (value "LED1608")
      (footprint "eagle-import:LED1608")
      (libsource (lib "eagle-import") (part "LED1608"))
    )
    (comp (ref "LED46")
      (value "LED1608")
      (footprint "eagle-import:LED1608")
      (libsource (lib "eagle-import") (part "LED1608"))
    )
    (comp (ref "LED47")
      (value "LED1608")
      (footprint "eagle-import:LED1608")
      (libsource (lib "eagle-import") (part "LED1608"))
    )
    (comp (ref "LED48")
      (value "LED1608")
      (footprint "eagle-import:LED1608")
      (libsource (lib "eagle-import") (part "LED1608"))
    )
    (comp (ref "LED49")
      (value "LED1608")
      (footprint "eagle-import:LED1608")
      (libsource (lib "eagle-import") (part "LED1608"))
    )
    (comp (ref "R26")
      (value "300")
      (footprint "eagle-import:R0603")
      (libsource (lib "eagle-import") (part "R-EU_R0603"))
    )
    (comp (ref "R27")
      (value "300")
      (footprint "eagle-import:R0603")
      (libsource (lib "eagle-import") (part "R-EU_R0603"))
    )
    (comp (ref "R28")
      (value "300")
      (footprint "eagle-import:R0603")
      (libsource (lib "eagle-import") (part "R-EU_R0603"))
    )
    (comp (ref "R29")
      (value "300")
      (footprint "eagle-import:R0603")
      (libsource (lib "eagle-import") (part "R-EU_R0603"))
    )
    (comp (ref "R30")
      (value "300")
      (footprint "eagle-import:R0603")
      (libsource (lib "eagle-import") (part "R-EU_R0603"))
    )
    (comp (ref "R31")
      (value "300")
      (footprint "eagle-import:R0603")
      (libsource (lib "eagle-import") (part "R-EU_R0603"))
    )
    (comp (ref "R32")
      (value "300")
      (footprint "eagle-import:R0603")
      (libsource (lib "eagle-import") (part "R-EU_R0603"))
    )
    (comp (ref "R33")
      (value "1k")
      (footprint "eagle-import:R0603")
      (libsource (lib "eagle-import") (part "R-EU_R0603"))
    )
    (comp (ref "R34")
      (value "1k")
      (footprint "eagle-import:R0603")
      (libsource (lib "eagle-import") (part "R-EU_R0603"))
    )
    (comp (ref "R35")
      (value "1k")
      (footprint "eagle-import:R0603")
      (libsource (lib "eagle-import") (part "R-EU_R0603"))
    )
    (comp (ref "R36")
      (value "1k")
      (footprint "eagle-import:R0603")
      (libsource (lib "eagle-import") (part "R-EU_R0603"))
    )
    (comp (ref "R37")
      (value "300")
      (footprint "eagle-import:R0603")
      (libsource (lib "eagle-import") (part "R-EU_R0603"))
    )
    (comp (ref "R38")
      (value "300")
      (footprint "eagle-import:R0603")
      (libsource (lib "eagle-import") (part "R-EU_R0603"))
    )
    (comp (ref "R39")
      (value "300")
      (footprint "eagle-import:R0603")
      (libsource (lib "eagle-import") (part "R-EU_R0603"))
    )
    (comp (ref "R40")
      (value "300")
      (footprint "eagle-import:R0603")
      (libsource (lib "eagle-import") (part "R-EU_R0603"))
    )
    (comp (ref "R41")
      (value "1k")
      (footprint "eagle-import:R0603")
      (libsource (lib "eagle-import") (part "R-EU_R0603"))
    )
    (comp (ref "R42")
      (value "1k")
      (footprint "eagle-import:R0603")
      (libsource (lib "eagle-import") (part "R-EU_R0603"))
    )
    (comp (ref "R43")
      (value "1k")
      (footprint "eagle-import:R0603")
      (libsource (lib "eagle-import") (part "R-EU_R0603"))
    )
    (comp (ref "R44")
      (value "1k")
      (footprint "eagle-import:R0603")
      (libsource (lib "eagle-import") (part "R-EU_R0603"))
    )
    (comp (ref "R77")
      (value "1k")
      (footprint "eagle-import:R0603")
      (libsource (lib "eagle-import") (part "R-EU_R0603"))
    )
    (comp (ref "R78")
      (value "1k")
      (footprint "eagle-import:R0603")
      (libsource (lib "eagle-import") (part "R-EU_R0603"))
    )
    (comp (ref "R79")
      (value "1k")
      (footprint "eagle-import:R0603")
      (libsource (lib "eagle-import") (part "R-EU_R0603"))
    )
    (comp (ref "R80")
      (value "1k")
      (footprint "eagle-import:R0603")
      (libsource (lib "eagle-import") (part "R-EU_R0603"))
    )
    (comp (ref "R81")
      (value "1k")
      (footprint "eagle-import:R0603")
      (libsource (lib "eagle-import") (part "R-EU_R0603"))
    )
    (comp (ref "R82")
      (value "1k")
      (footprint "eagle-import:R0603")
      (libsource (lib "eagle-import") (part "R-EU_R0603"))
    )
    (comp (ref "R83")
      (value "1k")
      (footprint "eagle-import:R0603")
      (libsource (lib "eagle-import") (part "R-EU_R0603"))
    )
    (comp (ref "R84")
      (value "1k")
      (footprint "eagle-import:R0603")
      (libsource (lib "eagle-import") (part "R-EU_R0603"))
    )
    (comp (ref "R85")
      (value "1k")
      (footprint "eagle-import:R0603")
      (libsource (lib "eagle-import") (part "R-EU_R0603"))
    )
    (comp (ref "R86")
      (value "1k")
      (footprint "eagle-import:R0603")
      (libsource (lib "eagle-import") (part "R-EU_R0603"))
    )
    (comp (ref "R87")
      (value "1k")
      (footprint "eagle-import:R0603")
      (libsource (lib "eagle-import") (part "R-EU_R0603"))
    )
    (comp (ref "R88")
      (value "1k")
      (footprint "eagle-import:R0603")
      (libsource (lib "eagle-import") (part "R-EU_R0603"))
    )
    (comp (ref "R89")
      (value "1k")
      (footprint "eagle-import:R0603")
      (libsource (lib "eagle-import") (part "R-EU_R0603"))
    )
    (comp (ref "R90")
      (value "1k")
      (footprint "eagle-import:R0603")
      (libsource (lib "eagle-import") (part "R-EU_R0603"))
    )
    (comp (ref "R91")
      (value "1k")
      (footprint "eagle-import:R0603")
      (libsource (lib "eagle-import") (part "R-EU_R0603"))
    )
    (comp (ref "R92")
      (value "1k")
      (footprint "eagle-import:R0603")
      (libsource (lib "eagle-import") (part "R-EU_R0603"))
    )
    (comp (ref "R93")
      (value "1k")
      (footprint "eagle-import:R0603")
      (libsource (lib "eagle-import") (part "R-EU_R0603"))
    )
    (comp (ref "R94")
      (value "1k")
      (footprint "eagle-import:R0603")
      (libsource (lib "eagle-import") (part "R-EU_R0603"))
    )
    (comp (ref "R95")
      (value "1k")
      (footprint "eagle-import:R0603")
      (libsource (lib "eagle-import") (part "R-EU_R0603"))
    )
    (comp (ref "R96")
      (value "1k")
      (footprint "eagle-import:R0603")
      (libsource (lib "eagle-import") (part "R-EU_R0603"))
    )
    (comp (ref "R97")
      (value "1k")
      (footprint "eagle-import:R0603")
      (libsource (lib "eagle-import") (part "R-EU_R0603"))
    )
    (comp (ref "R98")
      (value "1k")
      (footprint "eagle-import:R0603")
      (libsource (lib "eagle-import") (part "R-EU_R0603"))
    )
    (comp (ref "R99")
      (value "1k")
      (footprint "eagle-import:R0603")
      (libsource (lib "eagle-import") (part "R-EU_R0603"))
    )
    (comp (ref "R100")
      (value "1k")
      (footprint "eagle-import:R0603")
      (libsource (lib "eagle-import") (part "R-EU_R0603"))
    )
    (comp (ref "R101")
      (value "300")
      (footprint "eagle-import:R0603")
      (libsource (lib "eagle-import") (part "R-EU_R0603"))
    )
    (comp (ref "R102")
      (value "1k")
      (footprint "eagle-import:R0603")
      (libsource (lib "eagle-import") (part "R-EU_R0603"))
    )
    (comp (ref "R103")
      (value "1k")
      (footprint "eagle-import:R0603")
      (libsource (lib "eagle-import") (part "R-EU_R0603"))
    )
    (comp (ref "R104")
      (value "1k")
      (footprint "eagle-import:R0603")
      (libsource (lib "eagle-import") (part "R-EU_R0603"))
    )
    (comp (ref "R105")
      (value "1k")
      (footprint "eagle-import:R0603")
      (libsource (lib "eagle-import") (part "R-EU_R0603"))
    )
    (comp (ref "R106")
      (value "1k")
      (footprint "eagle-import:R0603")
      (libsource (lib "eagle-import") (part "R-EU_R0603"))
    )
    (comp (ref "R107")
      (value "1k")
      (footprint "eagle-import:R0603")
      (libsource (lib "eagle-import") (part "R-EU_R0603"))
    )
    (comp (ref "R108")
      (value "1k")
      (footprint "eagle-import:R0603")
      (libsource (lib "eagle-import") (part "R-EU_R0603"))
    )
    (comp (ref "R109")
      (value "1k")
      (footprint "eagle-import:R0603")
      (libsource (lib "eagle-import") (part "R-EU_R0603"))
    )
    (comp (ref "R110")
      (value "1k")
      (footprint "eagle-import:R0603")
      (libsource (lib "eagle-import") (part "R-EU_R0603"))
    )
    (comp (ref "R111")
      (value "1k")
      (footprint "eagle-import:R0603")
      (libsource (lib "eagle-import") (part "R-EU_R0603"))
    )
    (comp (ref "R112")
      (value "1k")
      (footprint "eagle-import:R0603")
      (libsource (lib "eagle-import") (part "R-EU_R0603"))
    )
    (comp (ref "R113")
      (value "1k")
      (footprint "eagle-import:R0603")
      (libsource (lib "eagle-import") (part "R-EU_R0603"))
    )
    (comp (ref "R114")
      (value "1k")
      (footprint "eagle-import:R0603")
      (libsource (lib "eagle-import") (part "R-EU_R0603"))
    )
    (comp (ref "R115")
      (value "1k")
      (footprint "eagle-import:R0603")
      (libsource (lib "eagle-import") (part "R-EU_R0603"))
    )
    (comp (ref "R116")
      (value "1k")
      (footprint "eagle-import:R0603")
      (libsource (lib "eagle-import") (part "R-EU_R0603"))
    )
    (comp (ref "R117")
      (value "1k")
      (footprint "eagle-import:R0603")
      (libsource (lib "eagle-import") (part "R-EU_R0603"))
    )
    (comp (ref "TR2")
      (value "2SC2712GR")
      (footprint "eagle-import:SOT-23")
      (libsource (lib "eagle-import") (part "SOT-23_NMOS"))
    )
    (comp (ref "TR3")
      (value "2SC2712GR")
      (footprint "eagle-import:SOT-23")
      (libsource (lib "eagle-import") (part "SOT-23_NMOS"))
    )
    (comp (ref "TR4")
      (value "2SC2712GR")
      (footprint "eagle-import:SOT-23")
      (libsource (lib "eagle-import") (part "SOT-23_NMOS"))
    )
    (comp (ref "TR15")
      (value "2SC2712GR")
      (footprint "eagle-import:SOT-23")
      (libsource (lib "eagle-import") (part "SOT-23_NMOS"))
    )
    (comp (ref "TR16")
      (value "2SC2712GR")
      (footprint "eagle-import:SOT-23")
      (libsource (lib "eagle-import") (part "SOT-23_NMOS"))
    )
    (comp (ref "TR18")
      (value "2SC2712GR")
      (footprint "eagle-import:SOT-23")
      (libsource (lib "eagle-import") (part "SOT-23_NMOS"))
    )
    (comp (ref "TR19")
      (value "2SC2712GR")
      (footprint "eagle-import:SOT-23")
      (libsource (lib "eagle-import") (part "SOT-23_NMOS"))
    )
    (comp (ref "TR20")
      (value "2SC2712GR")
      (footprint "eagle-import:SOT-23")
      (libsource (lib "eagle-import") (part "SOT-23_NMOS"))
    )
    (comp (ref "TR23")
      (value "2SC2712GR")
      (footprint "eagle-import:SOT-23")
      (libsource (lib "eagle-import") (part "SOT-23_NMOS"))
    )
    (comp (ref "TR24")
      (value "2SC2712GR")
      (footprint "eagle-import:SOT-23")
      (libsource (lib "eagle-import") (part "SOT-23_NMOS"))
    )
    (comp (ref "TR25")
      (value "2SC2712GR")
      (footprint "eagle-import:SOT-23")
      (libsource (lib "eagle-import") (part "SOT-23_NMOS"))
    )
    (comp (ref "TR26")
      (value "2SC2712GR")
      (footprint "eagle-import:SOT-23")
      (libsource (lib "eagle-import") (part "SOT-23_NMOS"))
    )
    (comp (ref "X2")
      (value "S3B-XH-A")
      (footprint "eagle-import:S3B-XH-A")
      (libsource (lib "eagle-import") (part "S3B-XH-A"))
    )
    (comp (ref "X3")
      (value "S3B-XH-A")
      (footprint "eagle-import:S3B-XH-A")
      (libsource (lib "eagle-import") (part "S3B-XH-A"))
    )
    (comp (ref "X4")
      (value "S3B-XH-A")
      (footprint "eagle-import:S3B-XH-A")
      (libsource (lib "eagle-import") (part "S3B-XH-A"))
    )
    (comp (ref "X13")
      (value "S3B-XH-A")
      (footprint "eagle-import:S3B-XH-A")
      (libsource (lib "eagle-import") (part "S3B-XH-A"))
    )
    (comp (ref "X14")
      (value "S3B-XH-A")
      (footprint "eagle-import:S3B-XH-A")
      (libsource (lib "eagle-import") (part "S3B-XH-A"))
    )
    (comp (ref "X15")
      (value "S3B-XH-A")
      (footprint "eagle-import:S3B-XH-A")
      (libsource (lib "eagle-import") (part "S3B-XH-A"))
    )
    (comp (ref "X16")
      (value "S3B-XH-A")
      (footprint "eagle-import:S3B-XH-A")
      (libsource (lib "eagle-import") (part "S3B-XH-A"))
    )
    (comp (ref "X17")
      (value "S3B-XH-A")
      (footprint "eagle-import:S3B-XH-A")
      (libsource (lib "eagle-import") (part "S3B-XH-A"))
    )
    (comp (ref "X20")
      (value "S3B-XH-A")
      (footprint "eagle-import:S3B-XH-A")
      (libsource (lib "eagle-import") (part "S3B-XH-A"))
    )
    (comp (ref "X21")
      (value "S3B-XH-A")
      (footprint "eagle-import:S3B-XH-A")
      (libsource (lib "eagle-import") (part "S3B-XH-A"))
    )
    (comp (ref "X23")
      (value "S3B-XH-A")
      (footprint "eagle-import:S3B-XH-A")
      (libsource (lib "eagle-import") (part "S3B-XH-A"))
    )
    (comp (ref "X24")
      (value "S3B-XH-A")
      (footprint "eagle-import:S3B-XH-A")
      (libsource (lib "eagle-import") (part "S3B-XH-A"))
    )
  )
  (nets
    (net (code "1") (name "3V3") (class "Default")
      (node (ref "C1") (pin "2") (pinfunction "2_2") (pintype "bidirectional"))
      (node (ref "C10") (pin "2") (pinfunction "2_2") (pintype "bidirectional"))
      (node (ref "C11") (pin "2") (pinfunction "2_2") (pintype "bidirectional"))
      (node (ref "C17") (pin "2") (pinfunction "2_2") (pintype "bidirectional"))
      (node (ref "C18") (pin "2") (pinfunction "2_2") (pintype "bidirectional"))
      (node (ref "C19") (pin "2") (pinfunction "2_2") (pintype "bidirectional"))
      (node (ref "C2") (pin "2") (pinfunction "2_2") (pintype "bidirectional"))
      (node (ref "C9") (pin "2") (pinfunction "2_2") (pintype "bidirectional"))
      (node (ref "IC1") (pin "1") (pinfunction "VBAT_1") (pintype "bidirectional"))
      (node (ref "IC1") (pin "13") (pinfunction "VDDA_13") (pintype "bidirectional"))
      (node (ref "IC1") (pin "19") (pinfunction "VDD_1_19") (pintype "bidirectional"))
      (node (ref "IC1") (pin "32") (pinfunction "VDD_2_32") (pintype "bidirectional"))
      (node (ref "IC1") (pin "48") (pinfunction "VDD_3_48") (pintype "bidirectional"))
      (node (ref "IC1") (pin "64") (pinfunction "VDD_4_64") (pintype "bidirectional"))
      (node (ref "IC4") (pin "1") (pinfunction "ANODE_1_1") (pintype "bidirectional"))
      (node (ref "IC4") (pin "3") (pinfunction "ANODE_2_3") (pintype "bidirectional"))
      (node (ref "IC4") (pin "5") (pinfunction "ANODE_3_5") (pintype "bidirectional"))
      (node (ref "IC4") (pin "7") (pinfunction "ANODE_4_7") (pintype "bidirectional"))
      (node (ref "IC5") (pin "1") (pinfunction "ANODE_1_1") (pintype "bidirectional"))
      (node (ref "IC5") (pin "3") (pinfunction "ANODE_2_3") (pintype "bidirectional"))
      (node (ref "IC5") (pin "5") (pinfunction "ANODE_3_5") (pintype "bidirectional"))
      (node (ref "IC5") (pin "7") (pinfunction "ANODE_4_7") (pintype "bidirectional"))
      (node (ref "IC7") (pin "1") (pinfunction "ANODE_1_1") (pintype "bidirectional"))
      (node (ref "IC7") (pin "3") (pinfunction "ANODE_2_3") (pintype "bidirectional"))
      (node (ref "IC7") (pin "5") (pinfunction "ANODE_3_5") (pintype "bidirectional"))
      (node (ref "IC7") (pin "7") (pinfunction "ANODE_4_7") (pintype "bidirectional"))
      (node (ref "IC8") (pin "1") (pinfunction "ANODE_1_1") (pintype "bidirectional"))
      (node (ref "IC8") (pin "3") (pinfunction "ANODE_2_3") (pintype "bidirectional"))
      (node (ref "IC8") (pin "5") (pinfunction "ANODE_3_5") (pintype "bidirectional"))
      (node (ref "IC8") (pin "7") (pinfunction "ANODE_4_7") (pintype "bidirectional"))
      (node (ref "IC9") (pin "1") (pinfunction "ANODE_1_1") (pintype "bidirectional"))
      (node (ref "IC9") (pin "3") (pinfunction "ANODE_2_3") (pintype "bidirectional"))
      (node (ref "IC9") (pin "5") (pinfunction "ANODE_3_5") (pintype "bidirectional"))
      (node (ref "IC9") (pin "7") (pinfunction "ANODE_4_7") (pintype "bidirectional"))
      (node (ref "LED3") (pin "A") (pinfunction "A_A") (pintype "passive"))
      (node (ref "R106") (pin "1") (pinfunction "1_1") (pintype "passive"))
      (node (ref "R108") (pin "1") (pinfunction "1_1") (pintype "passive"))
      (node (ref "R110") (pin "1") (pinfunction "1_1") (pintype "passive"))
      (node (ref "R112") (pin "1") (pinfunction "1_1") (pintype "passive"))
      (node (ref "R45") (pin "1") (pinfunction "1_1") (pintype "passive"))
      (node (ref "R55") (pin "1") (pinfunction "1_1") (pintype "passive"))
      (node (ref "R57") (pin "1") (pinfunction "1_1") (pintype "passive"))
      (node (ref "R67") (pin "1") (pinfunction "1_1") (pintype "passive"))
      (node (ref "R69") (pin "1") (pinfunction "1_1") (pintype "passive"))
      (node (ref "R71") (pin "1") (pinfunction "1_1") (pintype "passive"))
      (node (ref "R73") (pin "1") (pinfunction "1_1") (pintype "passive"))
      (node (ref "R75") (pin "1") (pinfunction "1_1") (pintype "passive"))
      (node (ref "R77") (pin "1") (pinfunction "1_1") (pintype "passive"))
      (node (ref "R87") (pin "1") (pinfunction "1_1") (pintype "passive"))
      (node (ref "R89") (pin "1") (pinfunction "1_1") (pintype "passive"))
      (node (ref "R91") (pin "1") (pinfunction "1_1") (pintype "passive"))
      (node (ref "R93") (pin "1") (pinfunction "1_1") (pintype "passive"))
      (node (ref "R95") (pin "1") (pinfunction "1_1") (pintype "passive"))
      (node (ref "R97") (pin "1") (pinfunction "1_1") (pintype "passive"))
      (node (ref "R99") (pin "1") (pinfunction "1_1") (pintype "passive"))
      (node (ref "S1") (pin "B1") (pinfunction "NO_2_B1") (pintype "bidirectional"))
      (node (ref "SL1") (pin "1") (pinfunction "1_1") (pintype "passive"))
      (node (ref "U1") (pin "2") (pinfunction "OUT_2") (pintype "output"))
      (node (ref "U1") (pin "4") (pinfunction "OUT_4") (pintype "output"))
      (node (ref "X22") (pin "2") (pinfunction "2_2") (pintype "passive"))
    )
    (net (code "2") (name "5V") (class "Default")
      (node (ref "C22") (pin "2") (pinfunction "2_2") (pintype "bidirectional"))
      (node (ref "IC2") (pin "3") (pinfunction "VCC_3") (pintype "bidirectional"))
      (node (ref "IC2") (pin "5") (pinfunction "EN_5") (pintype "bidirectional"))
      (node (ref "J2") (pin "1") (pinfunction "1_1") (pintype "bidirectional"))
      (node (ref "J2") (pin "5") (pinfunction "5_5") (pintype "bidirectional"))
      (node (ref "LED51-G") (pin "A") (pinfunction "A_A") (pintype "passive"))
      (node (ref "LED52-Y") (pin "A") (pinfunction "A_A") (pintype "passive"))
      (node (ref "R10") (pin "1") (pinfunction "1_1") (pintype "passive"))
      (node (ref "R2") (pin "1") (pinfunction "1_1") (pintype "passive"))
      (node (ref "R20") (pin "1") (pinfunction "1_1") (pintype "passive"))
      (node (ref "R60") (pin "1") (pinfunction "1_1") (pintype "passive"))
      (node (ref "R62") (pin "1") (pinfunction "1_1") (pintype "passive"))
      (node (ref "R64") (pin "1") (pinfunction "1_1") (pintype "passive"))
      (node (ref "R66") (pin "1") (pinfunction "1_1") (pintype "passive"))
      (node (ref "U1") (pin "3") (pinfunction "IN_3") (pintype "input"))
      (node (ref "X22") (pin "1") (pinfunction "1_1") (pintype "passive"))
    )
    (net (code "3") (name "12V") (class "Default")
      (node (ref "C5") (pin "1") (pinfunction "+_1") (pintype "bidirectional"))
      (node (ref "IC6") (pin "10") (pinfunction "COMMON_10") (pintype "bidirectional"))
      (node (ref "IC7") (pin "10") (pinfunction "COLLECTOR_1_10") (pintype "bidirectional"))
      (node (ref "IC7") (pin "12") (pinfunction "COLLECTOR_2_12") (pintype "bidirectional"))
      (node (ref "IC7") (pin "14") (pinfunction "COLLECTOR_3_14") (pintype "bidirectional"))
      (node (ref "IC7") (pin "16") (pinfunction "COLLECTOR_4_16") (pintype "bidirectional"))
      (node (ref "IC8") (pin "10") (pinfunction "COLLECTOR_1_10") (pintype "bidirectional"))
      (node (ref "IC8") (pin "12") (pinfunction "COLLECTOR_2_12") (pintype "bidirectional"))
      (node (ref "IC8") (pin "14") (pinfunction "COLLECTOR_3_14") (pintype "bidirectional"))
      (node (ref "IC8") (pin "16") (pinfunction "COLLECTOR_4_16") (pintype "bidirectional"))
      (node (ref "LED41") (pin "A") (pinfunction "A_A") (pintype "passive"))
      (node (ref "X1") (pin "1") (pinfunction "1_1") (pintype "passive"))
      (node (ref "X10") (pin "1") (pinfunction "1_1") (pintype "passive"))
      (node (ref "X11") (pin "1") (pinfunction "1_1") (pintype "passive"))
      (node (ref "X12") (pin "1") (pinfunction "1_1") (pintype "passive"))
      (node (ref "X25") (pin "1") (pinfunction "1_1") (pintype "passive"))
      (node (ref "X5") (pin "1") (pinfunction "1_1") (pintype "passive"))
      (node (ref "X6") (pin "1") (pinfunction "1_1") (pintype "passive"))
      (node (ref "X7") (pin "1") (pinfunction "1_1") (pintype "passive"))
      (node (ref "X9") (pin "1") (pinfunction "1_1") (pintype "passive"))
    )
    (net (code "4") (name "CANH") (class "Default")
      (node (ref "IC2") (pin "7") (pinfunction "CANH_7") (pintype "bidirectional"))
      (node (ref "J2") (pin "2") (pinfunction "2_2") (pintype "bidirectional"))
      (node (ref "J2") (pin "6") (pinfunction "6_6") (pintype "bidirectional"))
      (node (ref "R5") (pin "2") (pinfunction "2_2") (pintype "passive"))
    )
    (net (code "5") (name "CANL") (class "Default")
      (node (ref "IC2") (pin "6") (pinfunction "CANL_6") (pintype "bidirectional"))
      (node (ref "J2") (pin "3") (pinfunction "3_3") (pintype "bidirectional"))
      (node (ref "J2") (pin "7") (pinfunction "7_7") (pintype "bidirectional"))
      (node (ref "R5") (pin "1") (pinfunction "1_1") (pintype "passive"))
    )
    (net (code "6") (name "CAN_RX") (class "Default")
      (node (ref "IC1") (pin "44") (pinfunction "PA11_44") (pintype "bidirectional"))
      (node (ref "IC2") (pin "4") (pinfunction "RXD_4") (pintype "bidirectional"))
      (node (ref "R122") (pin "2") (pinfunction "2_2") (pintype "passive"))
    )
    (net (code "7") (name "CAN_TX") (class "Default")
      (node (ref "IC1") (pin "45") (pinfunction "PA12_45") (pintype "bidirectional"))
      (node (ref "IC2") (pin "1") (pinfunction "TXD_1") (pintype "bidirectional"))
      (node (ref "R121") (pin "2") (pinfunction "2_2") (pintype "passive"))
    )
    (net (code "8") (name "CATHODE-SE_1") (class "Default")
      (node (ref "LED35") (pin "K") (pinfunction "K_K") (pintype "passive"))
      (node (ref "R29") (pin "2") (pinfunction "2_2") (pintype "passive"))
      (node (ref "TR2") (pin "3") (pinfunction "D_3") (pintype "bidirectional"))
    )
    (net (code "9") (name "CATHODE-SE_2") (class "Default")
      (node (ref "LED37") (pin "K") (pinfunction "K_K") (pintype "passive"))
      (node (ref "R30") (pin "2") (pinfunction "2_2") (pintype "passive"))
      (node (ref "TR4") (pin "3") (pinfunction "D_3") (pintype "bidirectional"))
    )
    (net (code "10") (name "CATHODE-SE_3") (class "Default")
      (node (ref "LED44") (pin "K") (pinfunction "K_K") (pintype "passive"))
      (node (ref "R31") (pin "2") (pinfunction "2_2") (pintype "passive"))
      (node (ref "TR23") (pin "3") (pinfunction "D_3") (pintype "bidirectional"))
    )
    (net (code "11") (name "CATHODE-SE_4") (class "Default")
      (node (ref "LED7") (pin "K") (pinfunction "K_K") (pintype "passive"))
      (node (ref "R32") (pin "2") (pinfunction "2_2") (pintype "passive"))
      (node (ref "TR16") (pin "3") (pinfunction "D_3") (pintype "bidirectional"))
    )
    (net (code "12") (name "CATHODE-SE_5") (class "Default")
      (node (ref "LED33") (pin "K") (pinfunction "K_K") (pintype "passive"))
      (node (ref "R37") (pin "2") (pinfunction "2_2") (pintype "passive"))
      (node (ref "TR19") (pin "3") (pinfunction "D_3") (pintype "bidirectional"))
    )
    (net (code "13") (name "CATHODE-SE_6") (class "Default")
      (node (ref "LED42") (pin "K") (pinfunction "K_K") (pintype "passive"))
      (node (ref "R38") (pin "2") (pinfunction "2_2") (pintype "passive"))
      (node (ref "TR25") (pin "3") (pinfunction "D_3") (pintype "bidirectional"))
    )
    (net (code "14") (name "CATHODE-SE_7") (class "Default")
      (node (ref "LED36") (pin "K") (pinfunction "K_K") (pintype "passive"))
      (node (ref "R39") (pin "2") (pinfunction "2_2") (pintype "passive"))
      (node (ref "TR3") (pin "3") (pinfunction "D_3") (pintype "bidirectional"))
    )
    (net (code "15") (name "CATHODE-SE_8") (class "Default")
      (node (ref "LED38") (pin "K") (pinfunction "K_K") (pintype "passive"))
      (node (ref "R40") (pin "2") (pinfunction "2_2") (pintype "passive"))
      (node (ref "TR15") (pin "3") (pinfunction "D_3") (pintype "bidirectional"))
    )
    (net (code "16") (name "CATHODE-SE_9") (class "Default")
      (node (ref "LED45") (pin "K") (pinfunction "K_K") (pintype "passive"))
      (node (ref "R26") (pin "2") (pinfunction "2_2") (pintype "passive"))
      (node (ref "TR24") (pin "3") (pinfunction "D_3") (pintype "bidirectional"))
    )
    (net (code "17") (name "CATHODE-SE_10") (class "Default")
      (node (ref "LED32") (pin "K") (pinfunction "K_K") (pintype "passive"))
      (node (ref "R27") (pin "2") (pinfunction "2_2") (pintype "passive"))
      (node (ref "TR18") (pin "3") (pinfunction "D_3") (pintype "bidirectional"))
    )
    (net (code "18") (name "CATHODE-SE_11") (class "Default")
      (node (ref "LED34") (pin "K") (pinfunction "K_K") (pintype "passive"))
      (node (ref "R28") (pin "2") (pinfunction "2_2") (pintype "passive"))
      (node (ref "TR20") (pin "3") (pinfunction "D_3") (pintype "bidirectional"))
    )
    (net (code "19") (name "CATHODE-SE_12") (class "Default")
      (node (ref "LED43") (pin "K") (pinfunction "K_K") (pintype "passive"))
      (node (ref "R101") (pin "2") (pinfunction "2_2") (pintype "passive"))
      (node (ref "TR26") (pin "3") (pinfunction "D_3") (pintype "bidirectional"))
    )
    (net (code "20") (name "CATHODE-SO_1") (class "Default")
      (node (ref "LED24") (pin "K") (pinfunction "K_K") (pintype "passive"))
      (node (ref "R4") (pin "2") (pinfunction "2_2") (pintype "passive"))
      (node (ref "TR9") (pin "3") (pinfunction "D_3") (pintype "bidirectional"))
    )
    (net (code "21") (name "CATHODE-SO_2") (class "Default")
      (node (ref "LED25") (pin "K") (pinfunction "K_K") (pintype "passive"))
      (node (ref "R6") (pin "2") (pinfunction "2_2") (pintype "passive"))
      (node (ref "TR10") (pin "3") (pinfunction "D_3") (pintype "bidirectional"))
    )
    (net (code "22") (name "CATHODE-SO_3") (class "Default")
      (node (ref "LED26") (pin "K") (pinfunction "K_K") (pintype "passive"))
      (node (ref "R7") (pin "2") (pinfunction "2_2") (pintype "passive"))
      (node (ref "TR11") (pin "3") (pinfunction "D_3") (pintype "bidirectional"))
    )
    (net (code "23") (name "CATHODE-SO_4") (class "Default")
      (node (ref "LED27") (pin "K") (pinfunction "K_K") (pintype "passive"))
      (node (ref "R8") (pin "2") (pinfunction "2_2") (pintype "passive"))
      (node (ref "TR1") (pin "3") (pinfunction "D_3") (pintype "bidirectional"))
    )
    (net (code "24") (name "CATHODE-SO_5") (class "Default")
      (node (ref "LED39") (pin "K") (pinfunction "K_K") (pintype "passive"))
      (node (ref "R21") (pin "2") (pinfunction "2_2") (pintype "passive"))
      (node (ref "TR5") (pin "3") (pinfunction "D_3") (pintype "bidirectional"))
    )
    (net (code "25") (name "CATHODE-SO_6") (class "Default")
      (node (ref "LED21") (pin "K") (pinfunction "K_K") (pintype "passive"))
      (node (ref "R22") (pin "2") (pinfunction "2_2") (pintype "passive"))
      (node (ref "TR6") (pin "3") (pinfunction "D_3") (pintype "bidirectional"))
    )
    (net (code "26") (name "CATHODE-SO_7") (class "Default")
      (node (ref "LED22") (pin "K") (pinfunction "K_K") (pintype "passive"))
      (node (ref "R23") (pin "2") (pinfunction "2_2") (pintype "passive"))
      (node (ref "TR7") (pin "3") (pinfunction "D_3") (pintype "bidirectional"))
    )
    (net (code "27") (name "CATHODE-SO_8") (class "Default")
      (node (ref "LED23") (pin "K") (pinfunction "K_K") (pintype "passive"))
      (node (ref "R24") (pin "2") (pinfunction "2_2") (pintype "passive"))
      (node (ref "TR8") (pin "3") (pinfunction "D_3") (pintype "bidirectional"))
    )
    (net (code "28") (name "DCDC_OUT") (class "Default")
      (node (ref "IC4") (pin "10") (pinfunction "COLLECTOR_1_10") (pintype "bidirectional"))
      (node (ref "IC4") (pin "12") (pinfunction "COLLECTOR_2_12") (pintype "bidirectional"))
      (node (ref "IC4") (pin "14") (pinfunction "COLLECTOR_3_14") (pintype "bidirectional"))
      (node (ref "IC4") (pin "16") (pinfunction "COLLECTOR_4_16") (pintype "bidirectional"))
      (node (ref "IC5") (pin "10") (pinfunction "COLLECTOR_1_10") (pintype "bidirectional"))
      (node (ref "IC5") (pin "12") (pinfunction "COLLECTOR_2_12") (pintype "bidirectional"))
      (node (ref "IC5") (pin "14") (pinfunction "COLLECTOR_3_14") (pintype "bidirectional"))
      (node (ref "IC5") (pin "16") (pinfunction "COLLECTOR_4_16") (pintype "bidirectional"))
      (node (ref "IC9") (pin "10") (pinfunction "COLLECTOR_1_10") (pintype "bidirectional"))
      (node (ref "IC9") (pin "12") (pinfunction "COLLECTOR_2_12") (pintype "bidirectional"))
      (node (ref "IC9") (pin "14") (pinfunction "COLLECTOR_3_14") (pintype "bidirectional"))
      (node (ref "IC9") (pin "16") (pinfunction "COLLECTOR_4_16") (pintype "bidirectional"))
      (node (ref "R118") (pin "1") (pinfunction "1_1") (pintype "passive"))
      (node (ref "X13") (pin "1") (pinfunction "1_1") (pintype "passive"))
      (node (ref "X14") (pin "1") (pinfunction "1_1") (pintype "passive"))
      (node (ref "X15") (pin "1") (pinfunction "1_1") (pintype "passive"))
      (node (ref "X16") (pin "1") (pinfunction "1_1") (pintype "passive"))
      (node (ref "X17") (pin "1") (pinfunction "1_1") (pintype "passive"))
      (node (ref "X2") (pin "1") (pinfunction "1_1") (pintype "passive"))
      (node (ref "X20") (pin "1") (pinfunction "1_1") (pintype "passive"))
      (node (ref "X21") (pin "1") (pinfunction "1_1") (pintype "passive"))
      (node (ref "X23") (pin "1") (pinfunction "1_1") (pintype "passive"))
      (node (ref "X24") (pin "1") (pinfunction "1_1") (pintype "passive"))
      (node (ref "X3") (pin "1") (pinfunction "1_1") (pintype "passive"))
      (node (ref "X4") (pin "1") (pinfunction "1_1") (pintype "passive"))
    )
    (net (code "29") (name "GND") (class "Default")
      (node (ref "C1") (pin "1") (pinfunction "1_1") (pintype "bidirectional"))
      (node (ref "C10") (pin "1") (pinfunction "1_1") (pintype "bidirectional"))
      (node (ref "C11") (pin "1") (pinfunction "1_1") (pintype "bidirectional"))
      (node (ref "C17") (pin "1") (pinfunction "1_1") (pintype "bidirectional"))
      (node (ref "C18") (pin "1") (pinfunction "1_1") (pintype "bidirectional"))
      (node (ref "C19") (pin "1") (pinfunction "1_1") (pintype "bidirectional"))
      (node (ref "C2") (pin "1") (pinfunction "1_1") (pintype "bidirectional"))
      (node (ref "C22") (pin "1") (pinfunction "1_1") (pintype "bidirectional"))
      (node (ref "C23") (pin "1") (pinfunction "1_1") (pintype "bidirectional"))
      (node (ref "C9") (pin "1") (pinfunction "1_1") (pintype "bidirectional"))
      (node (ref "IC1") (pin "12") (pinfunction "VSSA/VREF-_12") (pintype "bidirectional"))
      (node (ref "IC1") (pin "31") (pinfunction "VSS_1_31") (pintype "bidirectional"))
      (node (ref "IC1") (pin "47") (pinfunction "VSS_2_47") (pintype "bidirectional"))
      (node (ref "IC1") (pin "63") (pinfunction "VSS_3_63") (pintype "bidirectional"))
      (node (ref "IC2") (pin "2") (pinfunction "GND_2") (pintype "bidirectional"))
      (node (ref "IC2") (pin "8") (pinfunction "S_8") (pintype "bidirectional"))
      (node (ref "J2") (pin "4") (pinfunction "4_4") (pintype "bidirectional"))
      (node (ref "J2") (pin "8") (pinfunction "8_8") (pintype "bidirectional"))
      (node (ref "LED2") (pin "K") (pinfunction "K_K") (pintype "passive"))
      (node (ref "Q10") (pin "2") (pinfunction "S_2") (pintype "bidirectional"))
      (node (ref "Q9") (pin "2") (pinfunction "S_2") (pintype "bidirectional"))
      (node (ref "R1") (pin "2") (pinfunction "2_2") (pintype "passive"))
      (node (ref "R3") (pin "2") (pinfunction "2_2") (pintype "passive"))
      (node (ref "S2") (pin "C1") (pinfunction "COM_1_C1") (pintype "bidirectional"))
      (node (ref "S2") (pin "D1") (pinfunction "COM_2_D1") (pintype "bidirectional"))
      (node (ref "SL1") (pin "3") (pinfunction "3_3") (pintype "passive"))
      (node (ref "TR1") (pin "2") (pinfunction "S_2") (pintype "bidirectional"))
      (node (ref "TR10") (pin "2") (pinfunction "S_2") (pintype "bidirectional"))
      (node (ref "TR11") (pin "2") (pinfunction "S_2") (pintype "bidirectional"))
      (node (ref "TR12") (pin "2") (pinfunction "S_2") (pintype "bidirectional"))
      (node (ref "TR13") (pin "2") (pinfunction "S_2") (pintype "bidirectional"))
      (node (ref "TR14") (pin "2") (pinfunction "S_2") (pintype "bidirectional"))
      (node (ref "TR15") (pin "2") (pinfunction "S_2") (pintype "bidirectional"))
      (node (ref "TR16") (pin "2") (pinfunction "S_2") (pintype "bidirectional"))
      (node (ref "TR17") (pin "2") (pinfunction "S_2") (pintype "bidirectional"))
      (node (ref "TR18") (pin "2") (pinfunction "S_2") (pintype "bidirectional"))
      (node (ref "TR19") (pin "2") (pinfunction "S_2") (pintype "bidirectional"))
      (node (ref "TR2") (pin "2") (pinfunction "S_2") (pintype "bidirectional"))
      (node (ref "TR20") (pin "2") (pinfunction "S_2") (pintype "bidirectional"))
      (node (ref "TR21") (pin "2") (pinfunction "S_2") (pintype "bidirectional"))
      (node (ref "TR22") (pin "2") (pinfunction "S_2") (pintype "bidirectional"))
      (node (ref "TR23") (pin "2") (pinfunction "S_2") (pintype "bidirectional"))
      (node (ref "TR24") (pin "2") (pinfunction "S_2") (pintype "bidirectional"))
      (node (ref "TR25") (pin "2") (pinfunction "S_2") (pintype "bidirectional"))
      (node (ref "TR26") (pin "2") (pinfunction "S_2") (pintype "bidirectional"))
      (node (ref "TR3") (pin "2") (pinfunction "S_2") (pintype "bidirectional"))
      (node (ref "TR4") (pin "2") (pinfunction "S_2") (pintype "bidirectional"))
      (node (ref "TR5") (pin "2") (pinfunction "S_2") (pintype "bidirectional"))
      (node (ref "TR6") (pin "2") (pinfunction "S_2") (pintype "bidirectional"))
      (node (ref "TR7") (pin "2") (pinfunction "S_2") (pintype "bidirectional"))
      (node (ref "TR8") (pin "2") (pinfunction "S_2") (pintype "bidirectional"))
      (node (ref "TR9") (pin "2") (pinfunction "S_2") (pintype "bidirectional"))
      (node (ref "U1") (pin "1") (pinfunction "GND_1") (pintype "passive"))
      (node (ref "X22") (pin "3") (pinfunction "3_3") (pintype "passive"))
    )
    (net (code "30") (name "GND-M") (class "Default")
      (node (ref "C5") (pin "2") (pinfunction "-_2") (pintype "bidirectional"))
      (node (ref "IC6") (pin "9") (pinfunction "GND_9") (pintype "bidirectional"))
      (node (ref "LED50") (pin "K") (pinfunction "K_K") (pintype "passive"))
      (node (ref "R102") (pin "1") (pinfunction "1_1") (pintype "passive"))
      (node (ref "R103") (pin "1") (pinfunction "1_1") (pintype "passive"))
      (node (ref "R104") (pin "1") (pinfunction "1_1") (pintype "passive"))
      (node (ref "R105") (pin "1") (pinfunction "1_1") (pintype "passive"))
      (node (ref "R114") (pin "2") (pinfunction "2_2") (pintype "passive"))
      (node (ref "R115") (pin "2") (pinfunction "2_2") (pintype "passive"))
      (node (ref "R116") (pin "2") (pinfunction "2_2") (pintype "passive"))
      (node (ref "R117") (pin "2") (pinfunction "2_2") (pintype "passive"))
      (node (ref "R12") (pin "1") (pinfunction "1_1") (pintype "passive"))
      (node (ref "R13") (pin "1") (pinfunction "1_1") (pintype "passive"))
      (node (ref "R14") (pin "1") (pinfunction "1_1") (pintype "passive"))
      (node (ref "R15") (pin "1") (pinfunction "1_1") (pintype "passive"))
      (node (ref "R16") (pin "1") (pinfunction "1_1") (pintype "passive"))
      (node (ref "R17") (pin "1") (pinfunction "1_1") (pintype "passive"))
      (node (ref "R18") (pin "1") (pinfunction "1_1") (pintype "passive"))
      (node (ref "R19") (pin "1") (pinfunction "1_1") (pintype "passive"))
      (node (ref "R25") (pin "2") (pinfunction "2_2") (pintype "passive"))
      (node (ref "R33") (pin "1") (pinfunction "1_1") (pintype "passive"))
      (node (ref "R34") (pin "1") (pinfunction "1_1") (pintype "passive"))
      (node (ref "R35") (pin "1") (pinfunction "1_1") (pintype "passive"))
      (node (ref "R36") (pin "1") (pinfunction "1_1") (pintype "passive"))
      (node (ref "R41") (pin "1") (pinfunction "1_1") (pintype "passive"))
      (node (ref "R42") (pin "1") (pinfunction "1_1") (pintype "passive"))
      (node (ref "R43") (pin "1") (pinfunction "1_1") (pintype "passive"))
      (node (ref "R44") (pin "1") (pinfunction "1_1") (pintype "passive"))
      (node (ref "R46") (pin "2") (pinfunction "2_2") (pintype "passive"))
      (node (ref "R47") (pin "2") (pinfunction "2_2") (pintype "passive"))
      (node (ref "R48") (pin "2") (pinfunction "2_2") (pintype "passive"))
      (node (ref "R49") (pin "2") (pinfunction "2_2") (pintype "passive"))
      (node (ref "R50") (pin "2") (pinfunction "2_2") (pintype "passive"))
      (node (ref "R51") (pin "2") (pinfunction "2_2") (pintype "passive"))
      (node (ref "R52") (pin "2") (pinfunction "2_2") (pintype "passive"))
      (node (ref "R53") (pin "2") (pinfunction "2_2") (pintype "passive"))
      (node (ref "R78") (pin "2") (pinfunction "2_2") (pintype "passive"))
      (node (ref "R79") (pin "2") (pinfunction "2_2") (pintype "passive"))
      (node (ref "R80") (pin "2") (pinfunction "2_2") (pintype "passive"))
      (node (ref "R81") (pin "2") (pinfunction "2_2") (pintype "passive"))
      (node (ref "R82") (pin "2") (pinfunction "2_2") (pintype "passive"))
      (node (ref "R83") (pin "2") (pinfunction "2_2") (pintype "passive"))
      (node (ref "R84") (pin "2") (pinfunction "2_2") (pintype "passive"))
      (node (ref "R85") (pin "2") (pinfunction "2_2") (pintype "passive"))
      (node (ref "X13") (pin "3") (pinfunction "3_3") (pintype "passive"))
      (node (ref "X14") (pin "3") (pinfunction "3_3") (pintype "passive"))
      (node (ref "X15") (pin "3") (pinfunction "3_3") (pintype "passive"))
      (node (ref "X16") (pin "3") (pinfunction "3_3") (pintype "passive"))
      (node (ref "X17") (pin "3") (pinfunction "3_3") (pintype "passive"))
      (node (ref "X2") (pin "3") (pinfunction "3_3") (pintype "passive"))
      (node (ref "X20") (pin "3") (pinfunction "3_3") (pintype "passive"))
      (node (ref "X21") (pin "3") (pinfunction "3_3") (pintype "passive"))
      (node (ref "X23") (pin "3") (pinfunction "3_3") (pintype "passive"))
      (node (ref "X24") (pin "3") (pinfunction "3_3") (pintype "passive"))
      (node (ref "X25") (pin "2") (pinfunction "2_2") (pintype "passive"))
      (node (ref "X3") (pin "3") (pinfunction "3_3") (pintype "passive"))
      (node (ref "X4") (pin "3") (pinfunction "3_3") (pintype "passive"))
    )
    (net (code "31") (name "NRST") (class "Default")
      (node (ref "C23") (pin "2") (pinfunction "2_2") (pintype "bidirectional"))
      (node (ref "IC1") (pin "7") (pinfunction "NRST_7") (pintype "bidirectional"))
      (node (ref "S2") (pin "A1") (pinfunction "NO_1_A1") (pintype "bidirectional"))
      (node (ref "SL1") (pin "5") (pinfunction "5_5") (pintype "passive"))
    )
    (net (code "32") (name "Net-(IC1-BOOT0)") (class "Default")
      (node (ref "IC1") (pin "60") (pinfunction "BOOT0_60") (pintype "bidirectional"))
      (node (ref "R1") (pin "1") (pinfunction "1_1") (pintype "passive"))
    )
    (net (code "33") (name "Net-(IC4-CATHODE_1)") (class "Default")
      (node (ref "IC4") (pin "2") (pinfunction "CATHODE_1_2") (pintype "bidirectional"))
      (node (ref "R37") (pin "1") (pinfunction "1_1") (pintype "passive"))
    )
    (net (code "34") (name "Net-(IC4-CATHODE_2)") (class "Default")
      (node (ref "IC4") (pin "4") (pinfunction "CATHODE_2_4") (pintype "bidirectional"))
      (node (ref "R38") (pin "1") (pinfunction "1_1") (pintype "passive"))
    )
    (net (code "35") (name "Net-(IC4-CATHODE_3)") (class "Default")
      (node (ref "IC4") (pin "6") (pinfunction "CATHODE_3_6") (pintype "bidirectional"))
      (node (ref "R39") (pin "1") (pinfunction "1_1") (pintype "passive"))
    )
    (net (code "36") (name "Net-(IC4-CATHODE_4)") (class "Default")
      (node (ref "IC4") (pin "8") (pinfunction "CATHODE_4_8") (pintype "bidirectional"))
      (node (ref "R40") (pin "1") (pinfunction "1_1") (pintype "passive"))
    )
    (net (code "37") (name "Net-(IC5-CATHODE_1)") (class "Default")
      (node (ref "IC5") (pin "2") (pinfunction "CATHODE_1_2") (pintype "bidirectional"))
      (node (ref "R26") (pin "1") (pinfunction "1_1") (pintype "passive"))
    )
    (net (code "38") (name "Net-(IC5-CATHODE_2)") (class "Default")
      (node (ref "IC5") (pin "4") (pinfunction "CATHODE_2_4") (pintype "bidirectional"))
      (node (ref "R27") (pin "1") (pinfunction "1_1") (pintype "passive"))
    )
    (net (code "39") (name "Net-(IC5-CATHODE_3)") (class "Default")
      (node (ref "IC5") (pin "6") (pinfunction "CATHODE_3_6") (pintype "bidirectional"))
      (node (ref "R28") (pin "1") (pinfunction "1_1") (pintype "passive"))
    )
    (net (code "40") (name "Net-(IC5-CATHODE_4)") (class "Default")
      (node (ref "IC5") (pin "8") (pinfunction "CATHODE_4_8") (pintype "bidirectional"))
      (node (ref "R101") (pin "1") (pinfunction "1_1") (pintype "passive"))
    )
    (net (code "41") (name "Net-(IC7-CATHODE_1)") (class "Default")
      (node (ref "IC7") (pin "2") (pinfunction "CATHODE_1_2") (pintype "bidirectional"))
      (node (ref "R4") (pin "1") (pinfunction "1_1") (pintype "passive"))
    )
    (net (code "42") (name "Net-(IC7-CATHODE_2)") (class "Default")
      (node (ref "IC7") (pin "4") (pinfunction "CATHODE_2_4") (pintype "bidirectional"))
      (node (ref "R6") (pin "1") (pinfunction "1_1") (pintype "passive"))
    )
    (net (code "43") (name "Net-(IC7-CATHODE_3)") (class "Default")
      (node (ref "IC7") (pin "6") (pinfunction "CATHODE_3_6") (pintype "bidirectional"))
      (node (ref "R7") (pin "1") (pinfunction "1_1") (pintype "passive"))
    )
    (net (code "44") (name "Net-(IC7-CATHODE_4)") (class "Default")
      (node (ref "IC7") (pin "8") (pinfunction "CATHODE_4_8") (pintype "bidirectional"))
      (node (ref "R8") (pin "1") (pinfunction "1_1") (pintype "passive"))
    )
    (net (code "45") (name "Net-(IC8-CATHODE_1)") (class "Default")
      (node (ref "IC8") (pin "2") (pinfunction "CATHODE_1_2") (pintype "bidirectional"))
      (node (ref "R21") (pin "1") (pinfunction "1_1") (pintype "passive"))
    )
    (net (code "46") (name "Net-(IC8-CATHODE_2)") (class "Default")
      (node (ref "IC8") (pin "4") (pinfunction "CATHODE_2_4") (pintype "bidirectional"))
      (node (ref "R22") (pin "1") (pinfunction "1_1") (pintype "passive"))
    )
    (net (code "47") (name "Net-(IC8-CATHODE_3)") (class "Default")
      (node (ref "IC8") (pin "6") (pinfunction "CATHODE_3_6") (pintype "bidirectional"))
      (node (ref "R23") (pin "1") (pinfunction "1_1") (pintype "passive"))
    )
    (net (code "48") (name "Net-(IC8-CATHODE_4)") (class "Default")
      (node (ref "IC8") (pin "8") (pinfunction "CATHODE_4_8") (pintype "bidirectional"))
      (node (ref "R24") (pin "1") (pinfunction "1_1") (pintype "passive"))
    )
    (net (code "49") (name "Net-(IC9-CATHODE_1)") (class "Default")
      (node (ref "IC9") (pin "2") (pinfunction "CATHODE_1_2") (pintype "bidirectional"))
      (node (ref "R29") (pin "1") (pinfunction "1_1") (pintype "passive"))
    )
    (net (code "50") (name "Net-(IC9-CATHODE_2)") (class "Default")
      (node (ref "IC9") (pin "4") (pinfunction "CATHODE_2_4") (pintype "bidirectional"))
      (node (ref "R30") (pin "1") (pinfunction "1_1") (pintype "passive"))
    )
    (net (code "51") (name "Net-(IC9-CATHODE_3)") (class "Default")
      (node (ref "IC9") (pin "6") (pinfunction "CATHODE_3_6") (pintype "bidirectional"))
      (node (ref "R31") (pin "1") (pinfunction "1_1") (pintype "passive"))
    )
    (net (code "52") (name "Net-(IC9-CATHODE_4)") (class "Default")
      (node (ref "IC9") (pin "8") (pinfunction "CATHODE_4_8") (pintype "bidirectional"))
      (node (ref "R32") (pin "1") (pinfunction "1_1") (pintype "passive"))
    )
    (net (code "53") (name "Net-(LED1-PadK)") (class "Default")
      (node (ref "LED1") (pin "K") (pinfunction "K_K") (pintype "passive"))
      (node (ref "R46") (pin "1") (pinfunction "1_1") (pintype "passive"))
    )
    (net (code "54") (name "Net-(LED2-PadA)") (class "Default")
      (node (ref "LED2") (pin "A") (pinfunction "A_A") (pintype "passive"))
      (node (ref "R2") (pin "2") (pinfunction "2_2") (pintype "passive"))
    )
    (net (code "55") (name "Net-(LED3-PadK)") (class "Default")
      (node (ref "LED3") (pin "K") (pinfunction "K_K") (pintype "passive"))
      (node (ref "R3") (pin "1") (pinfunction "1_1") (pintype "passive"))
    )
    (net (code "56") (name "Net-(LED4-PadK)") (class "Default")
      (node (ref "LED4") (pin "K") (pinfunction "K_K") (pintype "passive"))
      (node (ref "R47") (pin "1") (pinfunction "1_1") (pintype "passive"))
    )
    (net (code "57") (name "Net-(LED5-PadK)") (class "Default")
      (node (ref "LED5") (pin "K") (pinfunction "K_K") (pintype "passive"))
      (node (ref "R48") (pin "1") (pinfunction "1_1") (pintype "passive"))
    )
    (net (code "58") (name "Net-(LED6-PadK)") (class "Default")
      (node (ref "LED6") (pin "K") (pinfunction "K_K") (pintype "passive"))
      (node (ref "R78") (pin "1") (pinfunction "1_1") (pintype "passive"))
    )
    (net (code "59") (name "Net-(LED7-PadA)") (class "Default")
      (node (ref "LED7") (pin "A") (pinfunction "A_A") (pintype "passive"))
      (node (ref "R93") (pin "2") (pinfunction "2_2") (pintype "passive"))
    )
    (net (code "60") (name "Net-(LED8-PadK)") (class "Default")
      (node (ref "LED8") (pin "K") (pinfunction "K_K") (pintype "passive"))
      (node (ref "R79") (pin "1") (pinfunction "1_1") (pintype "passive"))
    )
    (net (code "61") (name "Net-(LED9-PadK)") (class "Default")
      (node (ref "LED9") (pin "K") (pinfunction "K_K") (pintype "passive"))
      (node (ref "R49") (pin "1") (pinfunction "1_1") (pintype "passive"))
    )
    (net (code "62") (name "Net-(LED10-PadK)") (class "Default")
      (node (ref "LED10") (pin "K") (pinfunction "K_K") (pintype "passive"))
      (node (ref "R50") (pin "1") (pinfunction "1_1") (pintype "passive"))
    )
    (net (code "63") (name "Net-(LED11-PadK)") (class "Default")
      (node (ref "LED11") (pin "K") (pinfunction "K_K") (pintype "passive"))
      (node (ref "R51") (pin "1") (pinfunction "1_1") (pintype "passive"))
    )
    (net (code "64") (name "Net-(LED12-PadK)") (class "Default")
      (node (ref "LED12") (pin "K") (pinfunction "K_K") (pintype "passive"))
      (node (ref "R52") (pin "1") (pinfunction "1_1") (pintype "passive"))
    )
    (net (code "65") (name "Net-(LED13-PadK)") (class "Default")
      (node (ref "LED13") (pin "K") (pinfunction "K_K") (pintype "passive"))
      (node (ref "R53") (pin "1") (pinfunction "1_1") (pintype "passive"))
    )
    (net (code "66") (name "Net-(LED14-PadA)") (class "Default")
      (node (ref "LED14") (pin "A") (pinfunction "A_A") (pintype "passive"))
      (node (ref "R60") (pin "2") (pinfunction "2_2") (pintype "passive"))
    )
    (net (code "67") (name "Net-(LED15-PadA)") (class "Default")
      (node (ref "LED15") (pin "A") (pinfunction "A_A") (pintype "passive"))
      (node (ref "R62") (pin "2") (pinfunction "2_2") (pintype "passive"))
    )
    (net (code "68") (name "Net-(LED16-PadA)") (class "Default")
      (node (ref "LED16") (pin "A") (pinfunction "A_A") (pintype "passive"))
      (node (ref "R64") (pin "2") (pinfunction "2_2") (pintype "passive"))
    )
    (net (code "69") (name "Net-(LED17-PadA)") (class "Default")
      (node (ref "LED17") (pin "A") (pinfunction "A_A") (pintype "passive"))
      (node (ref "R66") (pin "2") (pinfunction "2_2") (pintype "passive"))
    )
    (net (code "70") (name "Net-(LED18-PadK)") (class "Default")
      (node (ref "LED18") (pin "K") (pinfunction "K_K") (pintype "passive"))
      (node (ref "R80") (pin "1") (pinfunction "1_1") (pintype "passive"))
    )
    (net (code "71") (name "Net-(LED19-PadK)") (class "Default")
      (node (ref "LED19") (pin "K") (pinfunction "K_K") (pintype "passive"))
      (node (ref "R81") (pin "1") (pinfunction "1_1") (pintype "passive"))
    )
    (net (code "72") (name "Net-(LED20-PadK)") (class "Default")
      (node (ref "LED20") (pin "K") (pinfunction "K_K") (pintype "passive"))
      (node (ref "R82") (pin "1") (pinfunction "1_1") (pintype "passive"))
    )
    (net (code "73") (name "Net-(LED21-PadA)") (class "Default")
      (node (ref "LED21") (pin "A") (pinfunction "A_A") (pintype "passive"))
      (node (ref "R71") (pin "2") (pinfunction "2_2") (pintype "passive"))
    )
    (net (code "74") (name "Net-(LED22-PadA)") (class "Default")
      (node (ref "LED22") (pin "A") (pinfunction "A_A") (pintype "passive"))
      (node (ref "R73") (pin "2") (pinfunction "2_2") (pintype "passive"))
    )
    (net (code "75") (name "Net-(LED23-PadA)") (class "Default")
      (node (ref "LED23") (pin "A") (pinfunction "A_A") (pintype "passive"))
      (node (ref "R75") (pin "2") (pinfunction "2_2") (pintype "passive"))
    )
    (net (code "76") (name "Net-(LED24-PadA)") (class "Default")
      (node (ref "LED24") (pin "A") (pinfunction "A_A") (pintype "passive"))
      (node (ref "R45") (pin "2") (pinfunction "2_2") (pintype "passive"))
    )
    (net (code "77") (name "Net-(LED25-PadA)") (class "Default")
      (node (ref "LED25") (pin "A") (pinfunction "A_A") (pintype "passive"))
      (node (ref "R55") (pin "2") (pinfunction "2_2") (pintype "passive"))
    )
    (net (code "78") (name "Net-(LED26-PadA)") (class "Default")
      (node (ref "LED26") (pin "A") (pinfunction "A_A") (pintype "passive"))
      (node (ref "R57") (pin "2") (pinfunction "2_2") (pintype "passive"))
    )
    (net (code "79") (name "Net-(LED27-PadA)") (class "Default")
      (node (ref "LED27") (pin "A") (pinfunction "A_A") (pintype "passive"))
      (node (ref "R67") (pin "2") (pinfunction "2_2") (pintype "passive"))
    )
    (net (code "80") (name "Net-(LED28-PadK)") (class "Default")
      (node (ref "LED28") (pin "K") (pinfunction "K_K") (pintype "passive"))
      (node (ref "R83") (pin "1") (pinfunction "1_1") (pintype "passive"))
    )
    (net (code "81") (name "Net-(LED29-PadA)") (class "Default")
      (node (ref "LED29") (pin "A") (pinfunction "A_A") (pintype "passive"))
      (node (ref "R10") (pin "2") (pinfunction "2_2") (pintype "passive"))
    )
    (net (code "82") (name "Net-(LED30-PadK)") (class "Default")
      (node (ref "LED30") (pin "K") (pinfunction "K_K") (pintype "passive"))
      (node (ref "R84") (pin "1") (pinfunction "1_1") (pintype "passive"))
    )
    (net (code "83") (name "Net-(LED31-PadK)") (class "Default")
      (node (ref "LED31") (pin "K") (pinfunction "K_K") (pintype "passive"))
      (node (ref "R85") (pin "1") (pinfunction "1_1") (pintype "passive"))
    )
    (net (code "84") (name "Net-(LED32-PadA)") (class "Default")
      (node (ref "LED32") (pin "A") (pinfunction "A_A") (pintype "passive"))
      (node (ref "R95") (pin "2") (pinfunction "2_2") (pintype "passive"))
    )
    (net (code "85") (name "Net-(LED33-PadA)") (class "Default")
      (node (ref "LED33") (pin "A") (pinfunction "A_A") (pintype "passive"))
      (node (ref "R97") (pin "2") (pinfunction "2_2") (pintype "passive"))
    )
    (net (code "86") (name "Net-(LED34-PadA)") (class "Default")
      (node (ref "LED34") (pin "A") (pinfunction "A_A") (pintype "passive"))
      (node (ref "R99") (pin "2") (pinfunction "2_2") (pintype "passive"))
    )
    (net (code "87") (name "Net-(LED35-PadA)") (class "Default")
      (node (ref "LED35") (pin "A") (pinfunction "A_A") (pintype "passive"))
      (node (ref "R77") (pin "2") (pinfunction "2_2") (pintype "passive"))
    )
    (net (code "88") (name "Net-(LED36-PadA)") (class "Default")
      (node (ref "LED36") (pin "A") (pinfunction "A_A") (pintype "passive"))
      (node (ref "R87") (pin "2") (pinfunction "2_2") (pintype "passive"))
    )
    (net (code "89") (name "Net-(LED37-PadA)") (class "Default")
      (node (ref "LED37") (pin "A") (pinfunction "A_A") (pintype "passive"))
      (node (ref "R89") (pin "2") (pinfunction "2_2") (pintype "passive"))
    )
    (net (code "90") (name "Net-(LED38-PadA)") (class "Default")
      (node (ref "LED38") (pin "A") (pinfunction "A_A") (pintype "passive"))
      (node (ref "R91") (pin "2") (pinfunction "2_2") (pintype "passive"))
    )
    (net (code "91") (name "Net-(LED39-PadA)") (class "Default")
      (node (ref "LED39") (pin "A") (pinfunction "A_A") (pintype "passive"))
      (node (ref "R69") (pin "2") (pinfunction "2_2") (pintype "passive"))
    )
    (net (code "92") (name "Net-(LED40-PadA)") (class "Default")
      (node (ref "LED40") (pin "A") (pinfunction "A_A") (pintype "passive"))
      (node (ref "R20") (pin "2") (pinfunction "2_2") (pintype "passive"))
    )
    (net (code "93") (name "Net-(LED41-PadK)") (class "Default")
      (node (ref "LED41") (pin "K") (pinfunction "K_K") (pintype "passive"))
      (node (ref "R25") (pin "1") (pinfunction "1_1") (pintype "passive"))
    )
    (net (code "94") (name "Net-(LED42-PadA)") (class "Default")
      (node (ref "LED42") (pin "A") (pinfunction "A_A") (pintype "passive"))
      (node (ref "R110") (pin "2") (pinfunction "2_2") (pintype "passive"))
    )
    (net (code "95") (name "Net-(LED43-PadA)") (class "Default")
      (node (ref "LED43") (pin "A") (pinfunction "A_A") (pintype "passive"))
      (node (ref "R112") (pin "2") (pinfunction "2_2") (pintype "passive"))
    )
    (net (code "96") (name "Net-(LED44-PadA)") (class "Default")
      (node (ref "LED44") (pin "A") (pinfunction "A_A") (pintype "passive"))
      (node (ref "R106") (pin "2") (pinfunction "2_2") (pintype "passive"))
    )
    (net (code "97") (name "Net-(LED45-PadA)") (class "Default")
      (node (ref "LED45") (pin "A") (pinfunction "A_A") (pintype "passive"))
      (node (ref "R108") (pin "2") (pinfunction "2_2") (pintype "passive"))
    )
    (net (code "98") (name "Net-(LED46-PadK)") (class "Default")
      (node (ref "LED46") (pin "K") (pinfunction "K_K") (pintype "passive"))
      (node (ref "R114") (pin "1") (pinfunction "1_1") (pintype "passive"))
    )
    (net (code "99") (name "Net-(LED47-PadK)") (class "Default")
      (node (ref "LED47") (pin "K") (pinfunction "K_K") (pintype "passive"))
      (node (ref "R115") (pin "1") (pinfunction "1_1") (pintype "passive"))
    )
    (net (code "100") (name "Net-(LED48-PadK)") (class "Default")
      (node (ref "LED48") (pin "K") (pinfunction "K_K") (pintype "passive"))
      (node (ref "R116") (pin "1") (pinfunction "1_1") (pintype "passive"))
    )
    (net (code "101") (name "Net-(LED49-PadK)") (class "Default")
      (node (ref "LED49") (pin "K") (pinfunction "K_K") (pintype "passive"))
      (node (ref "R117") (pin "1") (pinfunction "1_1") (pintype "passive"))
    )
    (net (code "102") (name "Net-(LED50-PadA)") (class "Default")
      (node (ref "LED50") (pin "A") (pinfunction "A_A") (pintype "passive"))
      (node (ref "R118") (pin "2") (pinfunction "2_2") (pintype "passive"))
    )
    (net (code "103") (name "Net-(LED51-G-PadK)") (class "Default")
      (node (ref "LED51-G") (pin "K") (pinfunction "K_K") (pintype "passive"))
      (node (ref "R119") (pin "1") (pinfunction "1_1") (pintype "passive"))
    )
    (net (code "104") (name "Net-(LED52-Y-PadK)") (class "Default")
      (node (ref "LED52-Y") (pin "K") (pinfunction "K_K") (pintype "passive"))
      (node (ref "R120") (pin "1") (pinfunction "1_1") (pintype "passive"))
    )
    (net (code "105") (name "Net-(Q9-D)") (class "Default")
      (node (ref "Q9") (pin "3") (pinfunction "D_3") (pintype "bidirectional"))
      (node (ref "R119") (pin "2") (pinfunction "2_2") (pintype "passive"))
    )
    (net (code "106") (name "Net-(Q9-G)") (class "Default")
      (node (ref "Q9") (pin "1") (pinfunction "G_1") (pintype "bidirectional"))
      (node (ref "R121") (pin "1") (pinfunction "1_1") (pintype "passive"))
    )
    (net (code "107") (name "Net-(Q10-D)") (class "Default")
      (node (ref "Q10") (pin "3") (pinfunction "D_3") (pintype "bidirectional"))
      (node (ref "R120") (pin "2") (pinfunction "2_2") (pintype "passive"))
    )
    (net (code "108") (name "Net-(Q10-G)") (class "Default")
      (node (ref "Q10") (pin "1") (pinfunction "G_1") (pintype "bidirectional"))
      (node (ref "R122") (pin "1") (pinfunction "1_1") (pintype "passive"))
    )
    (net (code "109") (name "Net-(TR1-G)") (class "Default")
      (node (ref "R68") (pin "2") (pinfunction "2_2") (pintype "passive"))
      (node (ref "TR1") (pin "1") (pinfunction "G_1") (pintype "bidirectional"))
    )
    (net (code "110") (name "Net-(TR2-G)") (class "Default")
      (node (ref "R86") (pin "2") (pinfunction "2_2") (pintype "passive"))
      (node (ref "TR2") (pin "1") (pinfunction "G_1") (pintype "bidirectional"))
    )
    (net (code "111") (name "Net-(TR3-G)") (class "Default")
      (node (ref "R88") (pin "2") (pinfunction "2_2") (pintype "passive"))
      (node (ref "TR3") (pin "1") (pinfunction "G_1") (pintype "bidirectional"))
    )
    (net (code "112") (name "Net-(TR4-G)") (class "Default")
      (node (ref "R90") (pin "2") (pinfunction "2_2") (pintype "passive"))
      (node (ref "TR4") (pin "1") (pinfunction "G_1") (pintype "bidirectional"))
    )
    (net (code "113") (name "Net-(TR5-G)") (class "Default")
      (node (ref "R70") (pin "2") (pinfunction "2_2") (pintype "passive"))
      (node (ref "TR5") (pin "1") (pinfunction "G_1") (pintype "bidirectional"))
    )
    (net (code "114") (name "Net-(TR6-G)") (class "Default")
      (node (ref "R72") (pin "2") (pinfunction "2_2") (pintype "passive"))
      (node (ref "TR6") (pin "1") (pinfunction "G_1") (pintype "bidirectional"))
    )
    (net (code "115") (name "Net-(TR7-G)") (class "Default")
      (node (ref "R74") (pin "2") (pinfunction "2_2") (pintype "passive"))
      (node (ref "TR7") (pin "1") (pinfunction "G_1") (pintype "bidirectional"))
    )
    (net (code "116") (name "Net-(TR8-G)") (class "Default")
      (node (ref "R76") (pin "2") (pinfunction "2_2") (pintype "passive"))
      (node (ref "TR8") (pin "1") (pinfunction "G_1") (pintype "bidirectional"))
    )
    (net (code "117") (name "Net-(TR9-G)") (class "Default")
      (node (ref "R54") (pin "2") (pinfunction "2_2") (pintype "passive"))
      (node (ref "TR9") (pin "1") (pinfunction "G_1") (pintype "bidirectional"))
    )
    (net (code "118") (name "Net-(TR10-G)") (class "Default")
      (node (ref "R56") (pin "2") (pinfunction "2_2") (pintype "passive"))
      (node (ref "TR10") (pin "1") (pinfunction "G_1") (pintype "bidirectional"))
    )
    (net (code "119") (name "Net-(TR11-G)") (class "Default")
      (node (ref "R58") (pin "2") (pinfunction "2_2") (pintype "passive"))
      (node (ref "TR11") (pin "1") (pinfunction "G_1") (pintype "bidirectional"))
    )
    (net (code "120") (name "Net-(TR12-D)") (class "Default")
      (node (ref "LED14") (pin "K") (pinfunction "K_K") (pintype "passive"))
      (node (ref "TR12") (pin "3") (pinfunction "D_3") (pintype "bidirectional"))
    )
    (net (code "121") (name "Net-(TR12-G)") (class "Default")
      (node (ref "R59") (pin "2") (pinfunction "2_2") (pintype "passive"))
      (node (ref "TR12") (pin "1") (pinfunction "G_1") (pintype "bidirectional"))
    )
    (net (code "122") (name "Net-(TR13-D)") (class "Default")
      (node (ref "LED15") (pin "K") (pinfunction "K_K") (pintype "passive"))
      (node (ref "TR13") (pin "3") (pinfunction "D_3") (pintype "bidirectional"))
    )
    (net (code "123") (name "Net-(TR13-G)") (class "Default")
      (node (ref "R61") (pin "2") (pinfunction "2_2") (pintype "passive"))
      (node (ref "TR13") (pin "1") (pinfunction "G_1") (pintype "bidirectional"))
    )
    (net (code "124") (name "Net-(TR14-D)") (class "Default")
      (node (ref "LED16") (pin "K") (pinfunction "K_K") (pintype "passive"))
      (node (ref "TR14") (pin "3") (pinfunction "D_3") (pintype "bidirectional"))
    )
    (net (code "125") (name "Net-(TR14-G)") (class "Default")
      (node (ref "R63") (pin "2") (pinfunction "2_2") (pintype "passive"))
      (node (ref "TR14") (pin "1") (pinfunction "G_1") (pintype "bidirectional"))
    )
    (net (code "126") (name "Net-(TR15-G)") (class "Default")
      (node (ref "R92") (pin "2") (pinfunction "2_2") (pintype "passive"))
      (node (ref "TR15") (pin "1") (pinfunction "G_1") (pintype "bidirectional"))
    )
    (net (code "127") (name "Net-(TR16-G)") (class "Default")
      (node (ref "R94") (pin "2") (pinfunction "2_2") (pintype "passive"))
      (node (ref "TR16") (pin "1") (pinfunction "G_1") (pintype "bidirectional"))
    )
    (net (code "128") (name "Net-(TR17-D)") (class "Default")
      (node (ref "LED17") (pin "K") (pinfunction "K_K") (pintype "passive"))
      (node (ref "TR17") (pin "3") (pinfunction "D_3") (pintype "bidirectional"))
    )
    (net (code "129") (name "Net-(TR17-G)") (class "Default")
      (node (ref "R65") (pin "2") (pinfunction "2_2") (pintype "passive"))
      (node (ref "TR17") (pin "1") (pinfunction "G_1") (pintype "bidirectional"))
    )
    (net (code "130") (name "Net-(TR18-G)") (class "Default")
      (node (ref "R96") (pin "2") (pinfunction "2_2") (pintype "passive"))
      (node (ref "TR18") (pin "1") (pinfunction "G_1") (pintype "bidirectional"))
    )
    (net (code "131") (name "Net-(TR19-G)") (class "Default")
      (node (ref "R98") (pin "2") (pinfunction "2_2") (pintype "passive"))
      (node (ref "TR19") (pin "1") (pinfunction "G_1") (pintype "bidirectional"))
    )
    (net (code "132") (name "Net-(TR20-G)") (class "Default")
      (node (ref "R100") (pin "2") (pinfunction "2_2") (pintype "passive"))
      (node (ref "TR20") (pin "1") (pinfunction "G_1") (pintype "bidirectional"))
    )
    (net (code "133") (name "Net-(TR21-D)") (class "Default")
      (node (ref "LED29") (pin "K") (pinfunction "K_K") (pintype "passive"))
      (node (ref "TR21") (pin "3") (pinfunction "D_3") (pintype "bidirectional"))
    )
    (net (code "134") (name "Net-(TR21-G)") (class "Default")
      (node (ref "R9") (pin "2") (pinfunction "2_2") (pintype "passive"))
      (node (ref "TR21") (pin "1") (pinfunction "G_1") (pintype "bidirectional"))
    )
    (net (code "135") (name "Net-(TR22-D)") (class "Default")
      (node (ref "LED40") (pin "K") (pinfunction "K_K") (pintype "passive"))
      (node (ref "TR22") (pin "3") (pinfunction "D_3") (pintype "bidirectional"))
    )
    (net (code "136") (name "Net-(TR22-G)") (class "Default")
      (node (ref "R11") (pin "2") (pinfunction "2_2") (pintype "passive"))
      (node (ref "TR22") (pin "1") (pinfunction "G_1") (pintype "bidirectional"))
    )
    (net (code "137") (name "Net-(TR23-G)") (class "Default")
      (node (ref "R107") (pin "2") (pinfunction "2_2") (pintype "passive"))
      (node (ref "TR23") (pin "1") (pinfunction "G_1") (pintype "bidirectional"))
    )
    (net (code "138") (name "Net-(TR24-G)") (class "Default")
      (node (ref "R109") (pin "2") (pinfunction "2_2") (pintype "passive"))
      (node (ref "TR24") (pin "1") (pinfunction "G_1") (pintype "bidirectional"))
    )
    (net (code "139") (name "Net-(TR25-G)") (class "Default")
      (node (ref "R111") (pin "2") (pinfunction "2_2") (pintype "passive"))
      (node (ref "TR25") (pin "1") (pinfunction "G_1") (pintype "bidirectional"))
    )
    (net (code "140") (name "Net-(TR26-G)") (class "Default")
      (node (ref "R113") (pin "2") (pinfunction "2_2") (pintype "passive"))
      (node (ref "TR26") (pin "1") (pinfunction "G_1") (pintype "bidirectional"))
    )
    (net (code "141") (name "PA8") (class "Default")
      (node (ref "IC1") (pin "41") (pinfunction "PA8_41") (pintype "bidirectional"))
      (node (ref "JP1") (pin "1") (pinfunction "1_1") (pintype "passive"))
    )
    (net (code "142") (name "PB5") (class "Default")
      (node (ref "IC1") (pin "57") (pinfunction "PB5_57") (pintype "bidirectional"))
      (node (ref "R61") (pin "1") (pinfunction "1_1") (pintype "passive"))
    )
    (net (code "143") (name "PB6") (class "Default")
      (node (ref "IC1") (pin "58") (pinfunction "PB6_58") (pintype "bidirectional"))
      (node (ref "R63") (pin "1") (pinfunction "1_1") (pintype "passive"))
    )
    (net (code "144") (name "PB7") (class "Default")
      (node (ref "IC1") (pin "59") (pinfunction "PB7_59") (pintype "bidirectional"))
      (node (ref "R65") (pin "1") (pinfunction "1_1") (pintype "passive"))
    )
    (net (code "145") (name "PB8") (class "Default")
      (node (ref "IC1") (pin "61") (pinfunction "PB8_61") (pintype "bidirectional"))
      (node (ref "R9") (pin "1") (pinfunction "1_1") (pintype "passive"))
    )
    (net (code "146") (name "PB12") (class "Default")
      (node (ref "IC1") (pin "33") (pinfunction "PB12_33") (pintype "bidirectional"))
      (node (ref "JP3") (pin "3") (pinfunction "3_3") (pintype "passive"))
    )
    (net (code "147") (name "PB13") (class "Default")
      (node (ref "IC1") (pin "34") (pinfunction "PB13_34") (pintype "bidirectional"))
      (node (ref "JP3") (pin "2") (pinfunction "2_2") (pintype "passive"))
    )
    (net (code "148") (name "PB14") (class "Default")
      (node (ref "IC1") (pin "35") (pinfunction "PB14_35") (pintype "bidirectional"))
      (node (ref "S1") (pin "C1") (pinfunction "COM_1_C1") (pintype "bidirectional"))
    )
    (net (code "149") (name "PB15") (class "Default")
      (node (ref "IC1") (pin "36") (pinfunction "PB15_36") (pintype "bidirectional"))
      (node (ref "JP2") (pin "3") (pinfunction "3_3") (pintype "passive"))
    )
    (net (code "150") (name "PC6") (class "Default")
      (node (ref "IC1") (pin "37") (pinfunction "PC6_37") (pintype "bidirectional"))
      (node (ref "JP2") (pin "2") (pinfunction "2_2") (pintype "passive"))
    )
    (net (code "151") (name "PC7") (class "Default")
      (node (ref "IC1") (pin "38") (pinfunction "PC7_38") (pintype "bidirectional"))
      (node (ref "JP2") (pin "1") (pinfunction "1_1") (pintype "passive"))
    )
    (net (code "152") (name "PC8") (class "Default")
      (node (ref "IC1") (pin "39") (pinfunction "PC8_39") (pintype "bidirectional"))
      (node (ref "JP1") (pin "3") (pinfunction "3_3") (pintype "passive"))
    )
    (net (code "153") (name "PC9") (class "Default")
      (node (ref "IC1") (pin "40") (pinfunction "PC9_40") (pintype "bidirectional"))
      (node (ref "JP1") (pin "2") (pinfunction "2_2") (pintype "passive"))
    )
    (net (code "154") (name "PC13") (class "Default")
      (node (ref "IC1") (pin "2") (pinfunction "PC13_2") (pintype "bidirectional"))
      (node (ref "R11") (pin "1") (pinfunction "1_1") (pintype "passive"))
    )
    (net (code "155") (name "PD2") (class "Default")
      (node (ref "IC1") (pin "54") (pinfunction "PD2_54") (pintype "bidirectional"))
      (node (ref "R59") (pin "1") (pinfunction "1_1") (pintype "passive"))
    )
    (net (code "156") (name "SCL") (class "Default")
      (node (ref "IC1") (pin "42") (pinfunction "PA9_42") (pintype "bidirectional"))
      (node (ref "X19") (pin "2") (pinfunction "2_2") (pintype "passive"))
    )
    (net (code "157") (name "SDA") (class "Default")
      (node (ref "IC1") (pin "43") (pinfunction "PA10_43") (pintype "bidirectional"))
      (node (ref "X19") (pin "1") (pinfunction "1_1") (pintype "passive"))
    )
    (net (code "158") (name "SERVO_1") (class "Default")
      (node (ref "IC9") (pin "15") (pinfunction "EMITTER_4_15") (pintype "bidirectional"))
      (node (ref "LED6") (pin "A") (pinfunction "A_A") (pintype "passive"))
      (node (ref "R33") (pin "2") (pinfunction "2_2") (pintype "passive"))
      (node (ref "X24") (pin "2") (pinfunction "2_2") (pintype "passive"))
    )
    (net (code "159") (name "SERVO_2") (class "Default")
      (node (ref "IC9") (pin "13") (pinfunction "EMITTER_3_13") (pintype "bidirectional"))
      (node (ref "LED8") (pin "A") (pinfunction "A_A") (pintype "passive"))
      (node (ref "R34") (pin "2") (pinfunction "2_2") (pintype "passive"))
      (node (ref "X23") (pin "2") (pinfunction "2_2") (pintype "passive"))
    )
    (net (code "160") (name "SERVO_3") (class "Default")
      (node (ref "IC9") (pin "11") (pinfunction "EMITTER_2_11") (pintype "bidirectional"))
      (node (ref "LED18") (pin "A") (pinfunction "A_A") (pintype "passive"))
      (node (ref "R35") (pin "2") (pinfunction "2_2") (pintype "passive"))
      (node (ref "X21") (pin "2") (pinfunction "2_2") (pintype "passive"))
    )
    (net (code "161") (name "SERVO_4") (class "Default")
      (node (ref "IC9") (pin "9") (pinfunction "EMITTER_1_9") (pintype "bidirectional"))
      (node (ref "LED19") (pin "A") (pinfunction "A_A") (pintype "passive"))
      (node (ref "R36") (pin "2") (pinfunction "2_2") (pintype "passive"))
      (node (ref "X20") (pin "2") (pinfunction "2_2") (pintype "passive"))
    )
    (net (code "162") (name "SERVO_5") (class "Default")
      (node (ref "IC4") (pin "15") (pinfunction "EMITTER_4_15") (pintype "bidirectional"))
      (node (ref "LED20") (pin "A") (pinfunction "A_A") (pintype "passive"))
      (node (ref "R41") (pin "2") (pinfunction "2_2") (pintype "passive"))
      (node (ref "X17") (pin "2") (pinfunction "2_2") (pintype "passive"))
    )
    (net (code "163") (name "SERVO_6") (class "Default")
      (node (ref "IC4") (pin "13") (pinfunction "EMITTER_3_13") (pintype "bidirectional"))
      (node (ref "LED28") (pin "A") (pinfunction "A_A") (pintype "passive"))
      (node (ref "R42") (pin "2") (pinfunction "2_2") (pintype "passive"))
      (node (ref "X16") (pin "2") (pinfunction "2_2") (pintype "passive"))
    )
    (net (code "164") (name "SERVO_7") (class "Default")
      (node (ref "IC4") (pin "11") (pinfunction "EMITTER_2_11") (pintype "bidirectional"))
      (node (ref "LED30") (pin "A") (pinfunction "A_A") (pintype "passive"))
      (node (ref "R43") (pin "2") (pinfunction "2_2") (pintype "passive"))
      (node (ref "X3") (pin "2") (pinfunction "2_2") (pintype "passive"))
    )
    (net (code "165") (name "SERVO_8") (class "Default")
      (node (ref "IC4") (pin "9") (pinfunction "EMITTER_1_9") (pintype "bidirectional"))
      (node (ref "LED31") (pin "A") (pinfunction "A_A") (pintype "passive"))
      (node (ref "R44") (pin "2") (pinfunction "2_2") (pintype "passive"))
      (node (ref "X2") (pin "2") (pinfunction "2_2") (pintype "passive"))
    )
    (net (code "166") (name "SERVO_9") (class "Default")
      (node (ref "IC5") (pin "15") (pinfunction "EMITTER_4_15") (pintype "bidirectional"))
      (node (ref "LED46") (pin "A") (pinfunction "A_A") (pintype "passive"))
      (node (ref "R102") (pin "2") (pinfunction "2_2") (pintype "passive"))
      (node (ref "X15") (pin "2") (pinfunction "2_2") (pintype "passive"))
    )
    (net (code "167") (name "SERVO_10") (class "Default")
      (node (ref "IC5") (pin "13") (pinfunction "EMITTER_3_13") (pintype "bidirectional"))
      (node (ref "LED47") (pin "A") (pinfunction "A_A") (pintype "passive"))
      (node (ref "R103") (pin "2") (pinfunction "2_2") (pintype "passive"))
      (node (ref "X14") (pin "2") (pinfunction "2_2") (pintype "passive"))
    )
    (net (code "168") (name "SERVO_11") (class "Default")
      (node (ref "IC5") (pin "11") (pinfunction "EMITTER_2_11") (pintype "bidirectional"))
      (node (ref "LED48") (pin "A") (pinfunction "A_A") (pintype "passive"))
      (node (ref "R104") (pin "2") (pinfunction "2_2") (pintype "passive"))
      (node (ref "X13") (pin "2") (pinfunction "2_2") (pintype "passive"))
    )
    (net (code "169") (name "SERVO_12") (class "Default")
      (node (ref "IC5") (pin "9") (pinfunction "EMITTER_1_9") (pintype "bidirectional"))
      (node (ref "LED49") (pin "A") (pinfunction "A_A") (pintype "passive"))
      (node (ref "R105") (pin "2") (pinfunction "2_2") (pintype "passive"))
      (node (ref "X4") (pin "2") (pinfunction "2_2") (pintype "passive"))
    )
    (net (code "170") (name "SIGNAL-SE_1") (class "Default")
      (node (ref "IC1") (pin "30") (pinfunction "PB11_30") (pintype "bidirectional"))
      (node (ref "R86") (pin "1") (pinfunction "1_1") (pintype "passive"))
    )
    (net (code "171") (name "SIGNAL-SE_2") (class "Default")
      (node (ref "IC1") (pin "29") (pinfunction "PB10_29") (pintype "bidirectional"))
      (node (ref "R90") (pin "1") (pinfunction "1_1") (pintype "passive"))
    )
    (net (code "172") (name "SIGNAL-SE_3") (class "Default")
      (node (ref "IC1") (pin "27") (pinfunction "PB1_27") (pintype "bidirectional"))
      (node (ref "R107") (pin "1") (pinfunction "1_1") (pintype "passive"))
    )
    (net (code "173") (name "SIGNAL-SE_4") (class "Default")
      (node (ref "IC1") (pin "26") (pinfunction "PB0_26") (pintype "bidirectional"))
      (node (ref "R94") (pin "1") (pinfunction "1_1") (pintype "passive"))
    )
    (net (code "174") (name "SIGNAL-SE_5") (class "Default")
      (node (ref "IC1") (pin "23") (pinfunction "PA7_23") (pintype "bidirectional"))
      (node (ref "R98") (pin "1") (pinfunction "1_1") (pintype "passive"))
    )
    (net (code "175") (name "SIGNAL-SE_6") (class "Default")
      (node (ref "IC1") (pin "22") (pinfunction "PA6_22") (pintype "bidirectional"))
      (node (ref "R111") (pin "1") (pinfunction "1_1") (pintype "passive"))
    )
    (net (code "176") (name "SIGNAL-SE_7") (class "Default")
      (node (ref "IC1") (pin "21") (pinfunction "PA5_21") (pintype "bidirectional"))
      (node (ref "R88") (pin "1") (pinfunction "1_1") (pintype "passive"))
    )
    (net (code "177") (name "SIGNAL-SE_8") (class "Default")
      (node (ref "IC1") (pin "20") (pinfunction "PA4_20") (pintype "bidirectional"))
      (node (ref "R92") (pin "1") (pinfunction "1_1") (pintype "passive"))
    )
    (net (code "178") (name "SIGNAL-SE_9") (class "Default")
      (node (ref "IC1") (pin "17") (pinfunction "PA3_17") (pintype "bidirectional"))
      (node (ref "R109") (pin "1") (pinfunction "1_1") (pintype "passive"))
    )
    (net (code "179") (name "SIGNAL-SE_10") (class "Default")
      (node (ref "IC1") (pin "16") (pinfunction "PA2_16") (pintype "bidirectional"))
      (node (ref "R96") (pin "1") (pinfunction "1_1") (pintype "passive"))
    )
    (net (code "180") (name "SIGNAL-SE_11") (class "Default")
      (node (ref "IC1") (pin "15") (pinfunction "PA1_15") (pintype "bidirectional"))
      (node (ref "R100") (pin "1") (pinfunction "1_1") (pintype "passive"))
    )
    (net (code "181") (name "SIGNAL-SE_12") (class "Default")
      (node (ref "IC1") (pin "62") (pinfunction "PB9_62") (pintype "bidirectional"))
      (node (ref "R113") (pin "1") (pinfunction "1_1") (pintype "passive"))
    )
    (net (code "182") (name "SIGNAL-SO_1") (class "Default")
      (node (ref "IC1") (pin "11") (pinfunction "PC3_11") (pintype "bidirectional"))
      (node (ref "R54") (pin "1") (pinfunction "1_1") (pintype "passive"))
    )
    (net (code "183") (name "SIGNAL-SO_2") (class "Default")
      (node (ref "IC1") (pin "10") (pinfunction "PC2_10") (pintype "bidirectional"))
      (node (ref "R56") (pin "1") (pinfunction "1_1") (pintype "passive"))
    )
    (net (code "184") (name "SIGNAL-SO_3") (class "Default")
      (node (ref "IC1") (pin "9") (pinfunction "PC1_9") (pintype "bidirectional"))
      (node (ref "R58") (pin "1") (pinfunction "1_1") (pintype "passive"))
    )
    (net (code "185") (name "SIGNAL-SO_4") (class "Default")
      (node (ref "IC1") (pin "8") (pinfunction "PC0_8") (pintype "bidirectional"))
      (node (ref "R68") (pin "1") (pinfunction "1_1") (pintype "passive"))
    )
    (net (code "186") (name "SIGNAL-SO_5") (class "Default")
      (node (ref "IC1") (pin "6") (pinfunction "PF1/OSC_OUT_6") (pintype "bidirectional"))
      (node (ref "R70") (pin "1") (pinfunction "1_1") (pintype "passive"))
    )
    (net (code "187") (name "SIGNAL-SO_6") (class "Default")
      (node (ref "IC1") (pin "5") (pinfunction "PF0/OSC_IN_5") (pintype "bidirectional"))
      (node (ref "R72") (pin "1") (pinfunction "1_1") (pintype "passive"))
    )
    (net (code "188") (name "SIGNAL-SO_7") (class "Default")
      (node (ref "IC1") (pin "4") (pinfunction "PC15/OSC32_OUT_4") (pintype "bidirectional"))
      (node (ref "R74") (pin "1") (pinfunction "1_1") (pintype "passive"))
    )
    (net (code "189") (name "SIGNAL-SO_8") (class "Default")
      (node (ref "IC1") (pin "3") (pinfunction "PC14/OSC32_IN_3") (pintype "bidirectional"))
      (node (ref "R76") (pin "1") (pinfunction "1_1") (pintype "passive"))
    )
    (net (code "190") (name "SIGNAL_N1") (class "Default")
      (node (ref "IC6") (pin "1") (pinfunction "I1_1") (pintype "bidirectional"))
      (node (ref "IC7") (pin "15") (pinfunction "EMITTER_4_15") (pintype "bidirectional"))
      (node (ref "R12") (pin "2") (pinfunction "2_2") (pintype "passive"))
    )
    (net (code "191") (name "SIGNAL_N2") (class "Default")
      (node (ref "IC6") (pin "2") (pinfunction "I2_2") (pintype "bidirectional"))
      (node (ref "IC7") (pin "13") (pinfunction "EMITTER_3_13") (pintype "bidirectional"))
      (node (ref "R13") (pin "2") (pinfunction "2_2") (pintype "passive"))
    )
    (net (code "192") (name "SIGNAL_N3") (class "Default")
      (node (ref "IC6") (pin "3") (pinfunction "I3_3") (pintype "bidirectional"))
      (node (ref "IC7") (pin "11") (pinfunction "EMITTER_2_11") (pintype "bidirectional"))
      (node (ref "R14") (pin "2") (pinfunction "2_2") (pintype "passive"))
    )
    (net (code "193") (name "SIGNAL_N4") (class "Default")
      (node (ref "IC6") (pin "4") (pinfunction "I4_4") (pintype "bidirectional"))
      (node (ref "IC7") (pin "9") (pinfunction "EMITTER_1_9") (pintype "bidirectional"))
      (node (ref "R15") (pin "2") (pinfunction "2_2") (pintype "passive"))
    )
    (net (code "194") (name "SIGNAL_N5") (class "Default")
      (node (ref "IC6") (pin "5") (pinfunction "I5_5") (pintype "bidirectional"))
      (node (ref "IC8") (pin "15") (pinfunction "EMITTER_4_15") (pintype "bidirectional"))
      (node (ref "R16") (pin "2") (pinfunction "2_2") (pintype "passive"))
    )
    (net (code "195") (name "SIGNAL_N6") (class "Default")
      (node (ref "IC6") (pin "6") (pinfunction "I6_6") (pintype "bidirectional"))
      (node (ref "IC8") (pin "13") (pinfunction "EMITTER_3_13") (pintype "bidirectional"))
      (node (ref "R17") (pin "2") (pinfunction "2_2") (pintype "passive"))
    )
    (net (code "196") (name "SIGNAL_N7") (class "Default")
      (node (ref "IC6") (pin "7") (pinfunction "I7_7") (pintype "bidirectional"))
      (node (ref "IC8") (pin "11") (pinfunction "EMITTER_2_11") (pintype "bidirectional"))
      (node (ref "R18") (pin "2") (pinfunction "2_2") (pintype "passive"))
    )
    (net (code "197") (name "SIGNAL_N8") (class "Default")
      (node (ref "IC6") (pin "8") (pinfunction "I8_8") (pintype "bidirectional"))
      (node (ref "IC8") (pin "9") (pinfunction "EMITTER_1_9") (pintype "bidirectional"))
      (node (ref "R19") (pin "2") (pinfunction "2_2") (pintype "passive"))
    )
    (net (code "198") (name "SOLENOID_1") (class "Default")
      (node (ref "IC6") (pin "18") (pinfunction "O1_18") (pintype "bidirectional"))
      (node (ref "LED1") (pin "A") (pinfunction "A_A") (pintype "passive"))
      (node (ref "X5") (pin "2") (pinfunction "2_2") (pintype "passive"))
    )
    (net (code "199") (name "SOLENOID_2") (class "Default")
      (node (ref "IC6") (pin "17") (pinfunction "O2_17") (pintype "bidirectional"))
      (node (ref "LED4") (pin "A") (pinfunction "A_A") (pintype "passive"))
      (node (ref "X6") (pin "2") (pinfunction "2_2") (pintype "passive"))
    )
    (net (code "200") (name "SOLENOID_3") (class "Default")
      (node (ref "IC6") (pin "16") (pinfunction "O3_16") (pintype "bidirectional"))
      (node (ref "LED5") (pin "A") (pinfunction "A_A") (pintype "passive"))
      (node (ref "X7") (pin "2") (pinfunction "2_2") (pintype "passive"))
    )
    (net (code "201") (name "SOLENOID_4") (class "Default")
      (node (ref "IC6") (pin "15") (pinfunction "O4_15") (pintype "bidirectional"))
      (node (ref "LED9") (pin "A") (pinfunction "A_A") (pintype "passive"))
      (node (ref "X1") (pin "2") (pinfunction "2_2") (pintype "passive"))
    )
    (net (code "202") (name "SOLENOID_5") (class "Default")
      (node (ref "IC6") (pin "14") (pinfunction "O5_14") (pintype "bidirectional"))
      (node (ref "LED10") (pin "A") (pinfunction "A_A") (pintype "passive"))
      (node (ref "X9") (pin "2") (pinfunction "2_2") (pintype "passive"))
    )
    (net (code "203") (name "SOLENOID_6") (class "Default")
      (node (ref "IC6") (pin "13") (pinfunction "O6_13") (pintype "bidirectional"))
      (node (ref "LED11") (pin "A") (pinfunction "A_A") (pintype "passive"))
      (node (ref "X10") (pin "2") (pinfunction "2_2") (pintype "passive"))
    )
    (net (code "204") (name "SOLENOID_7") (class "Default")
      (node (ref "IC6") (pin "12") (pinfunction "O7_12") (pintype "bidirectional"))
      (node (ref "LED12") (pin "A") (pinfunction "A_A") (pintype "passive"))
      (node (ref "X11") (pin "2") (pinfunction "2_2") (pintype "passive"))
    )
    (net (code "205") (name "SOLENOID_8") (class "Default")
      (node (ref "IC6") (pin "11") (pinfunction "O8_11") (pintype "bidirectional"))
      (node (ref "LED13") (pin "A") (pinfunction "A_A") (pintype "passive"))
      (node (ref "X12") (pin "2") (pinfunction "2_2") (pintype "passive"))
    )
    (net (code "206") (name "SPI_MISO") (class "Default")
      (node (ref "IC1") (pin "52") (pinfunction "PC11_52") (pintype "bidirectional"))
      (node (ref "X8") (pin "2") (pinfunction "2_2") (pintype "passive"))
    )
    (net (code "207") (name "SPI_MOSI") (class "Default")
      (node (ref "IC1") (pin "53") (pinfunction "PC12_53") (pintype "bidirectional"))
      (node (ref "X8") (pin "1") (pinfunction "1_1") (pintype "passive"))
    )
    (net (code "208") (name "SPI_NSS") (class "Default")
      (node (ref "IC1") (pin "50") (pinfunction "PA15_50") (pintype "bidirectional"))
      (node (ref "X8") (pin "4") (pinfunction "4_4") (pintype "passive"))
    )
    (net (code "209") (name "SPI_SCK") (class "Default")
      (node (ref "IC1") (pin "51") (pinfunction "PC10_51") (pintype "bidirectional"))
      (node (ref "X8") (pin "3") (pinfunction "3_3") (pintype "passive"))
    )
    (net (code "210") (name "SWCLK") (class "Default")
      (node (ref "IC1") (pin "49") (pinfunction "PA14_49") (pintype "bidirectional"))
      (node (ref "SL1") (pin "2") (pinfunction "2_2") (pintype "passive"))
    )
    (net (code "211") (name "SWDIO") (class "Default")
      (node (ref "IC1") (pin "46") (pinfunction "PA13_46") (pintype "bidirectional"))
      (node (ref "SL1") (pin "4") (pinfunction "4_4") (pintype "passive"))
    )
    (net (code "212") (name "SWO") (class "Default")
      (node (ref "SL1") (pin "6") (pinfunction "6_6") (pintype "passive"))
    )
    (net (code "213") (name "USART_RX") (class "Default")
      (node (ref "IC1") (pin "56") (pinfunction "PB4_56") (pintype "bidirectional"))
      (node (ref "X18") (pin "2") (pinfunction "2_2") (pintype "passive"))
    )
    (net (code "214") (name "USART_TX") (class "Default")
      (node (ref "IC1") (pin "55") (pinfunction "PB3_55") (pintype "bidirectional"))
      (node (ref "X18") (pin "1") (pinfunction "1_1") (pintype "passive"))
    )
    (net (code "215") (name "unconnected-(IC1-PA0-Pad14)") (class "Default")
      (node (ref "IC1") (pin "14") (pinfunction "PA0_14") (pintype "bidirectional"))
    )
    (net (code "216") (name "unconnected-(IC1-PB2-Pad28)") (class "Default")
      (node (ref "IC1") (pin "28") (pinfunction "PB2_28") (pintype "bidirectional"))
    )
    (net (code "217") (name "unconnected-(IC1-PC4-Pad24)") (class "Default")
      (node (ref "IC1") (pin "24") (pinfunction "PC4_24") (pintype "bidirectional"))
    )
    (net (code "218") (name "unconnected-(IC1-PC5-Pad25)") (class "Default")
      (node (ref "IC1") (pin "25") (pinfunction "PC5_25") (pintype "bidirectional"))
    )
    (net (code "219") (name "unconnected-(IC1-PF4-Pad18)") (class "Default")
      (node (ref "IC1") (pin "18") (pinfunction "PF4_18") (pintype "bidirectional"))
    )
    (net (code "220") (name "unconnected-(J2-PadMH1)") (class "Default")
      (node (ref "J2") (pin "MH1") (pinfunction "MH1_MH1") (pintype "bidirectional"))
    )
    (net (code "221") (name "unconnected-(J2-PadMH2)") (class "Default")
      (node (ref "J2") (pin "MH2") (pinfunction "MH2_MH2") (pintype "bidirectional"))
    )
    (net (code "222") (name "unconnected-(J2-PadMH3)") (class "Default")
      (node (ref "J2") (pin "MH3") (pinfunction "MH3_MH3") (pintype "bidirectional"))
    )
    (net (code "223") (name "unconnected-(J2-PadMH4)") (class "Default")
      (node (ref "J2") (pin "MH4") (pinfunction "MH4_MH4") (pintype "bidirectional"))
    )
    (net (code "224") (name "unconnected-(JP3-Pad1)") (class "Default")
      (node (ref "JP3") (pin "1") (pinfunction "1_1") (pintype "passive"))
    )
    (net (code "225") (name "unconnected-(S1-COM_2-PadD1)") (class "Default")
      (node (ref "S1") (pin "D1") (pinfunction "COM_2_D1") (pintype "bidirectional"))
    )
    (net (code "226") (name "unconnected-(S1-NO_1-PadA1)") (class "Default")
      (node (ref "S1") (pin "A1") (pinfunction "NO_1_A1") (pintype "bidirectional"))
    )
    (net (code "227") (name "unconnected-(S2-NO_2-PadB1)") (class "Default")
      (node (ref "S2") (pin "B1") (pinfunction "NO_2_B1") (pintype "bidirectional"))
    )
  )
)
